# AllSerial.net
KiCad netlist of a schematic drawn in EAGLE
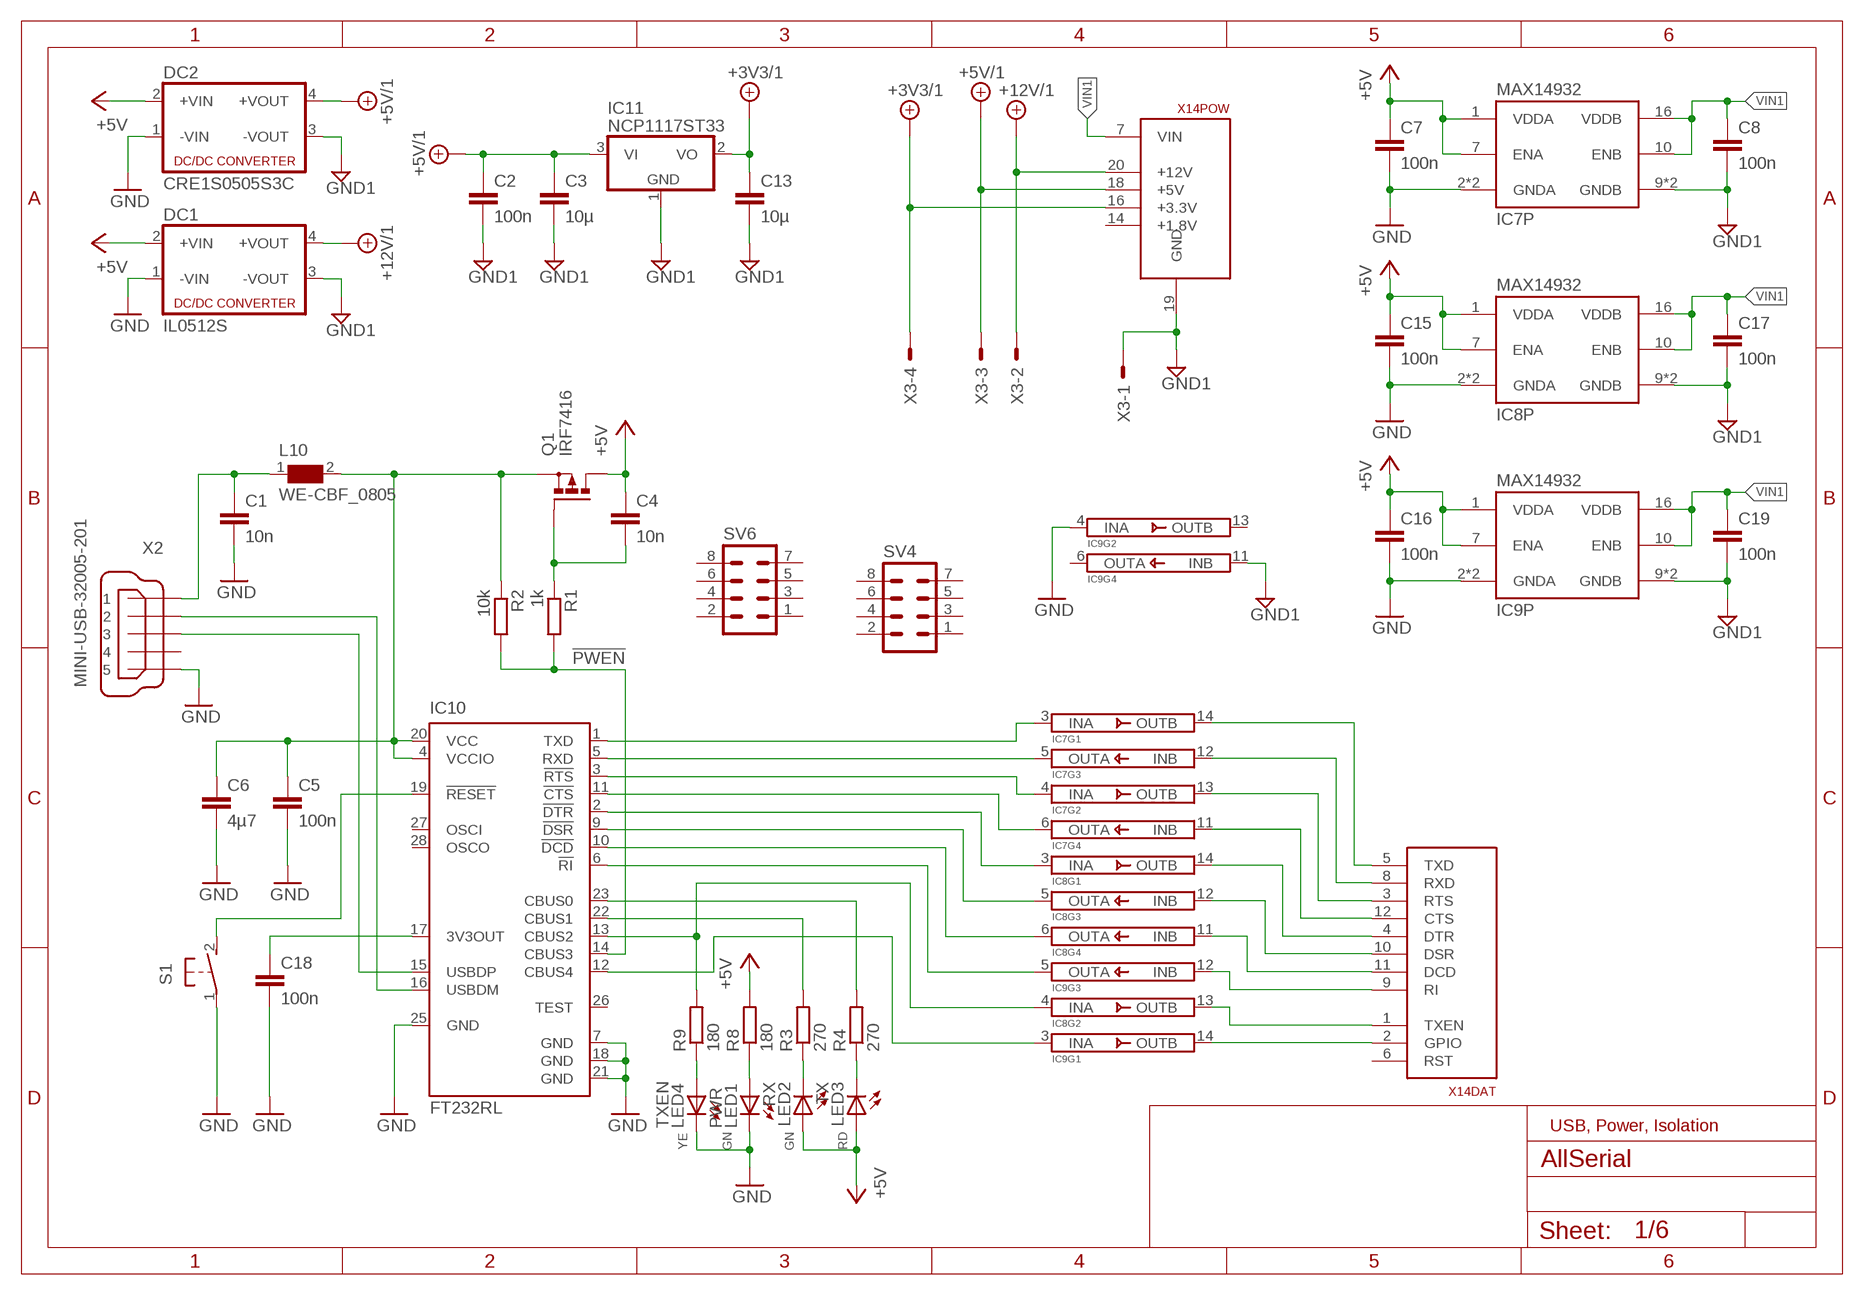
[diagram p0: schematic, sheet 1]
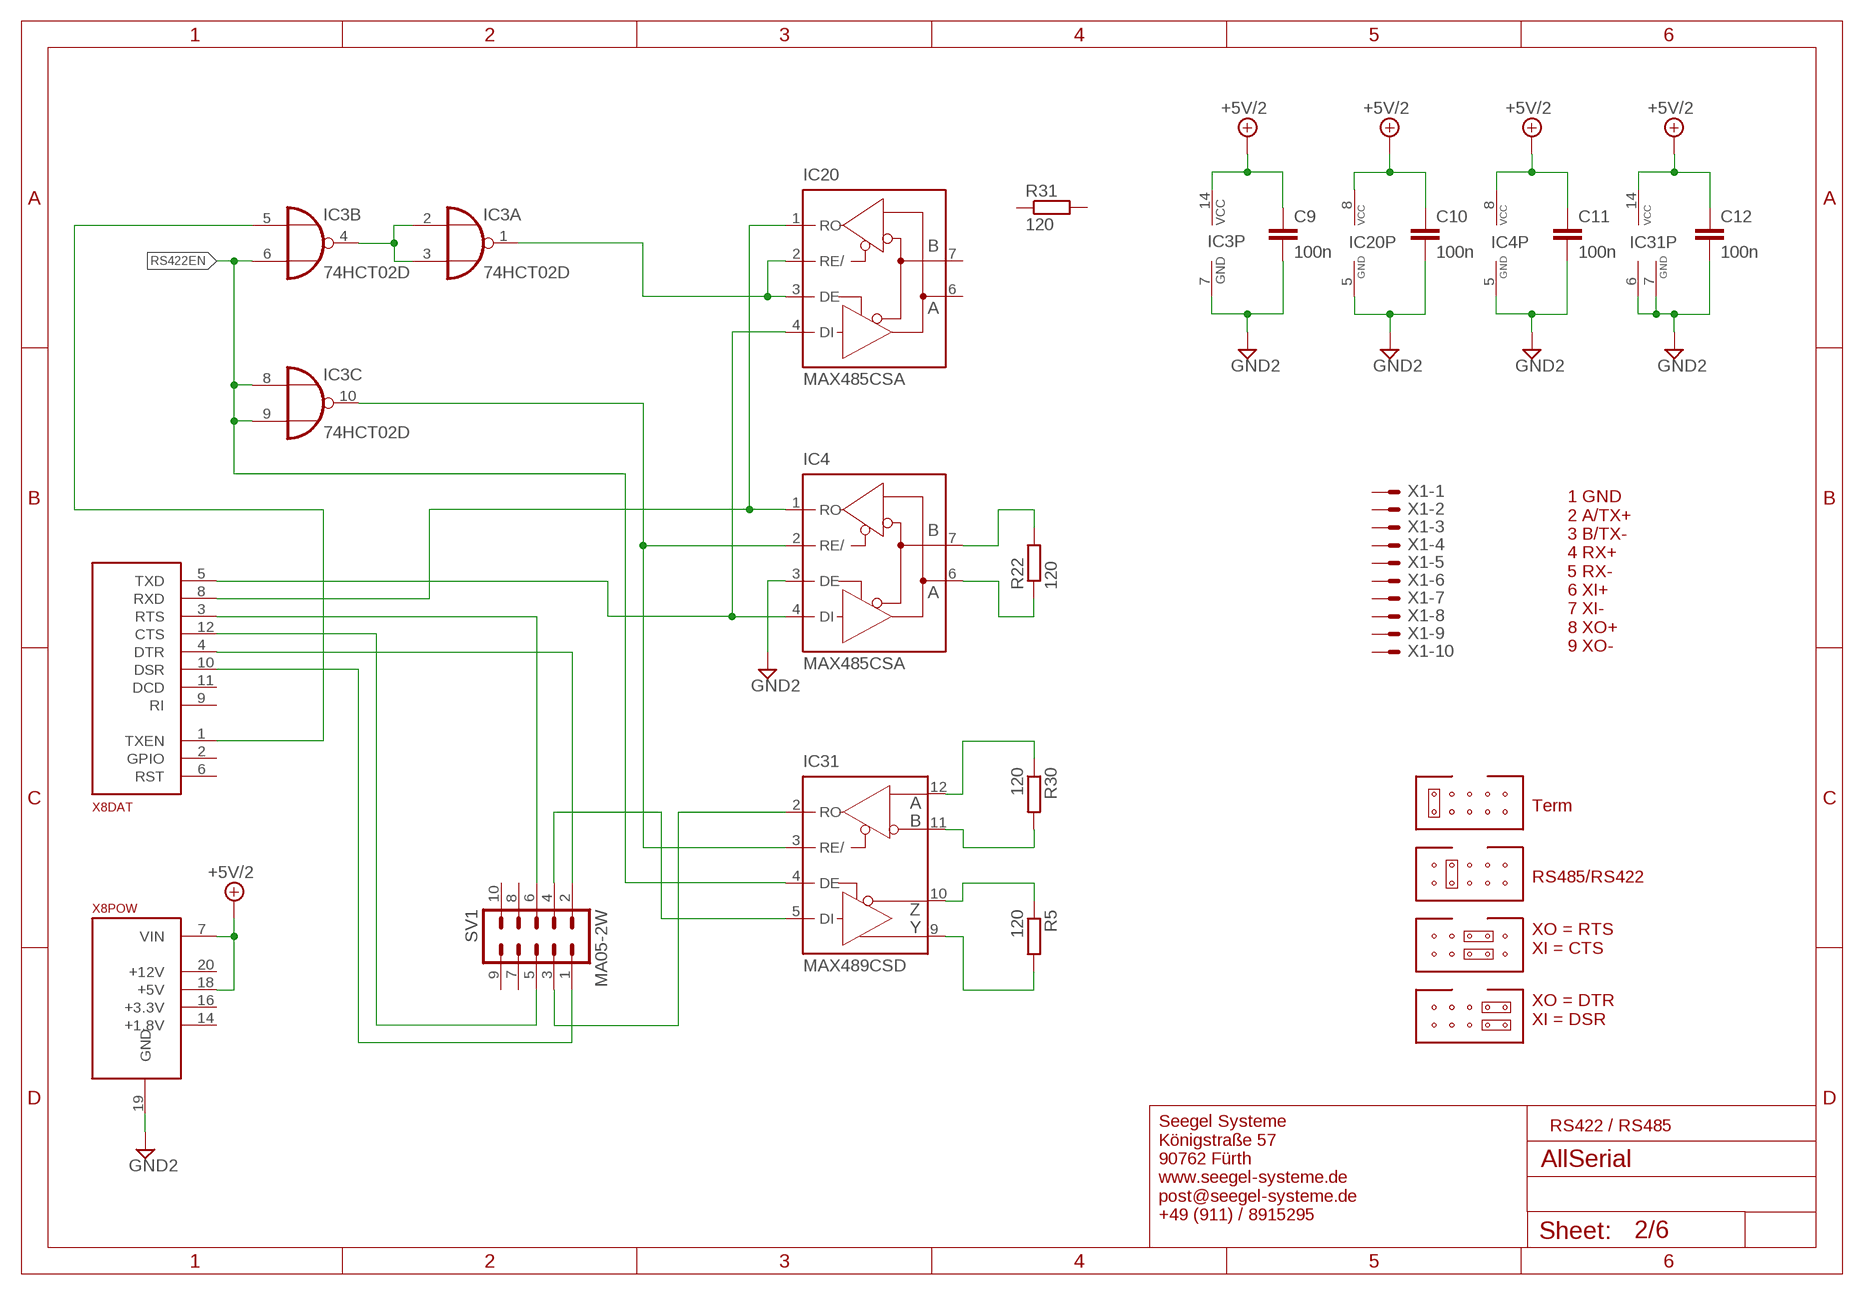
[diagram p1: schematic, sheet 2]
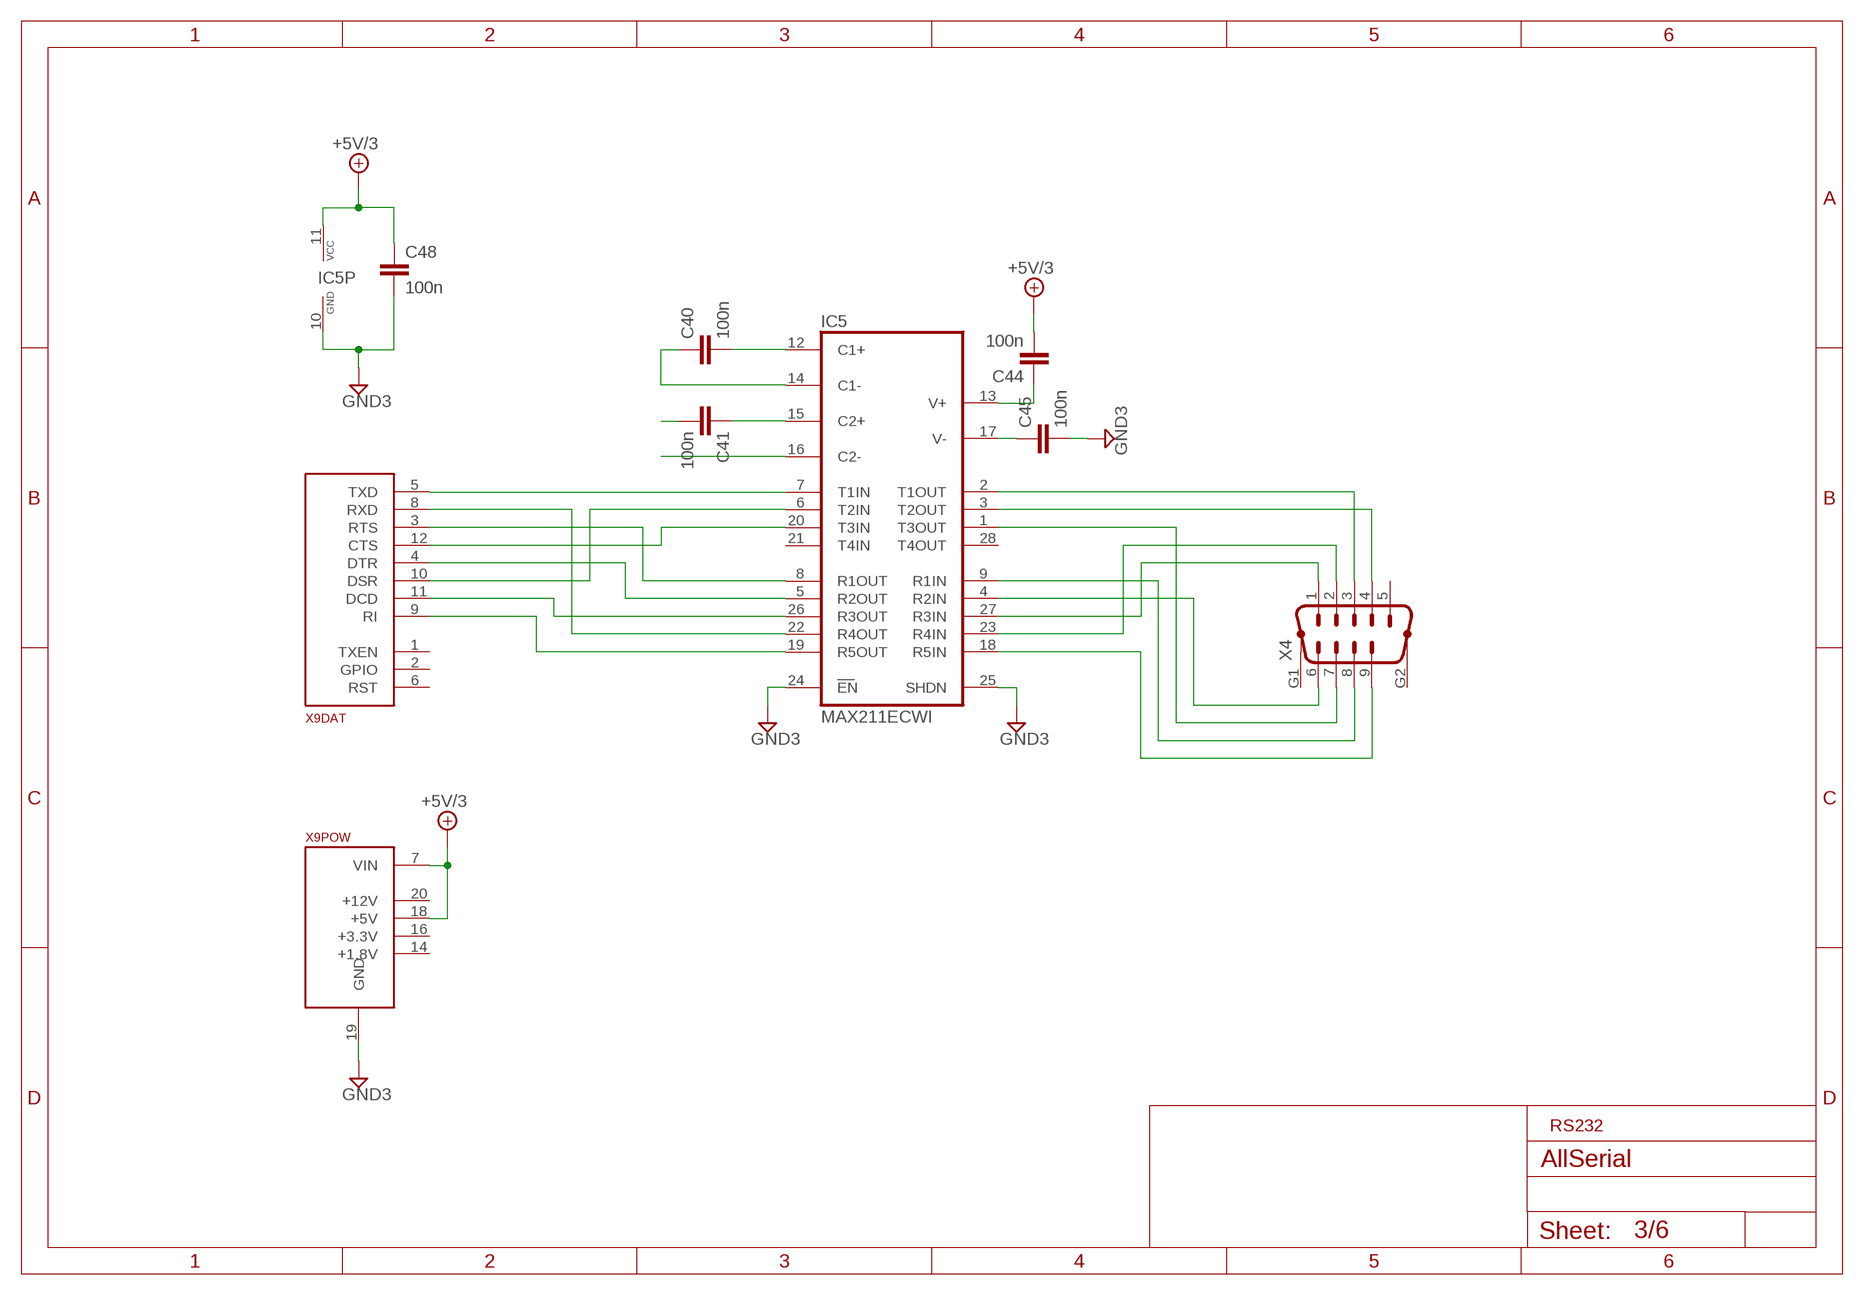
[diagram p2: schematic, sheet 3]
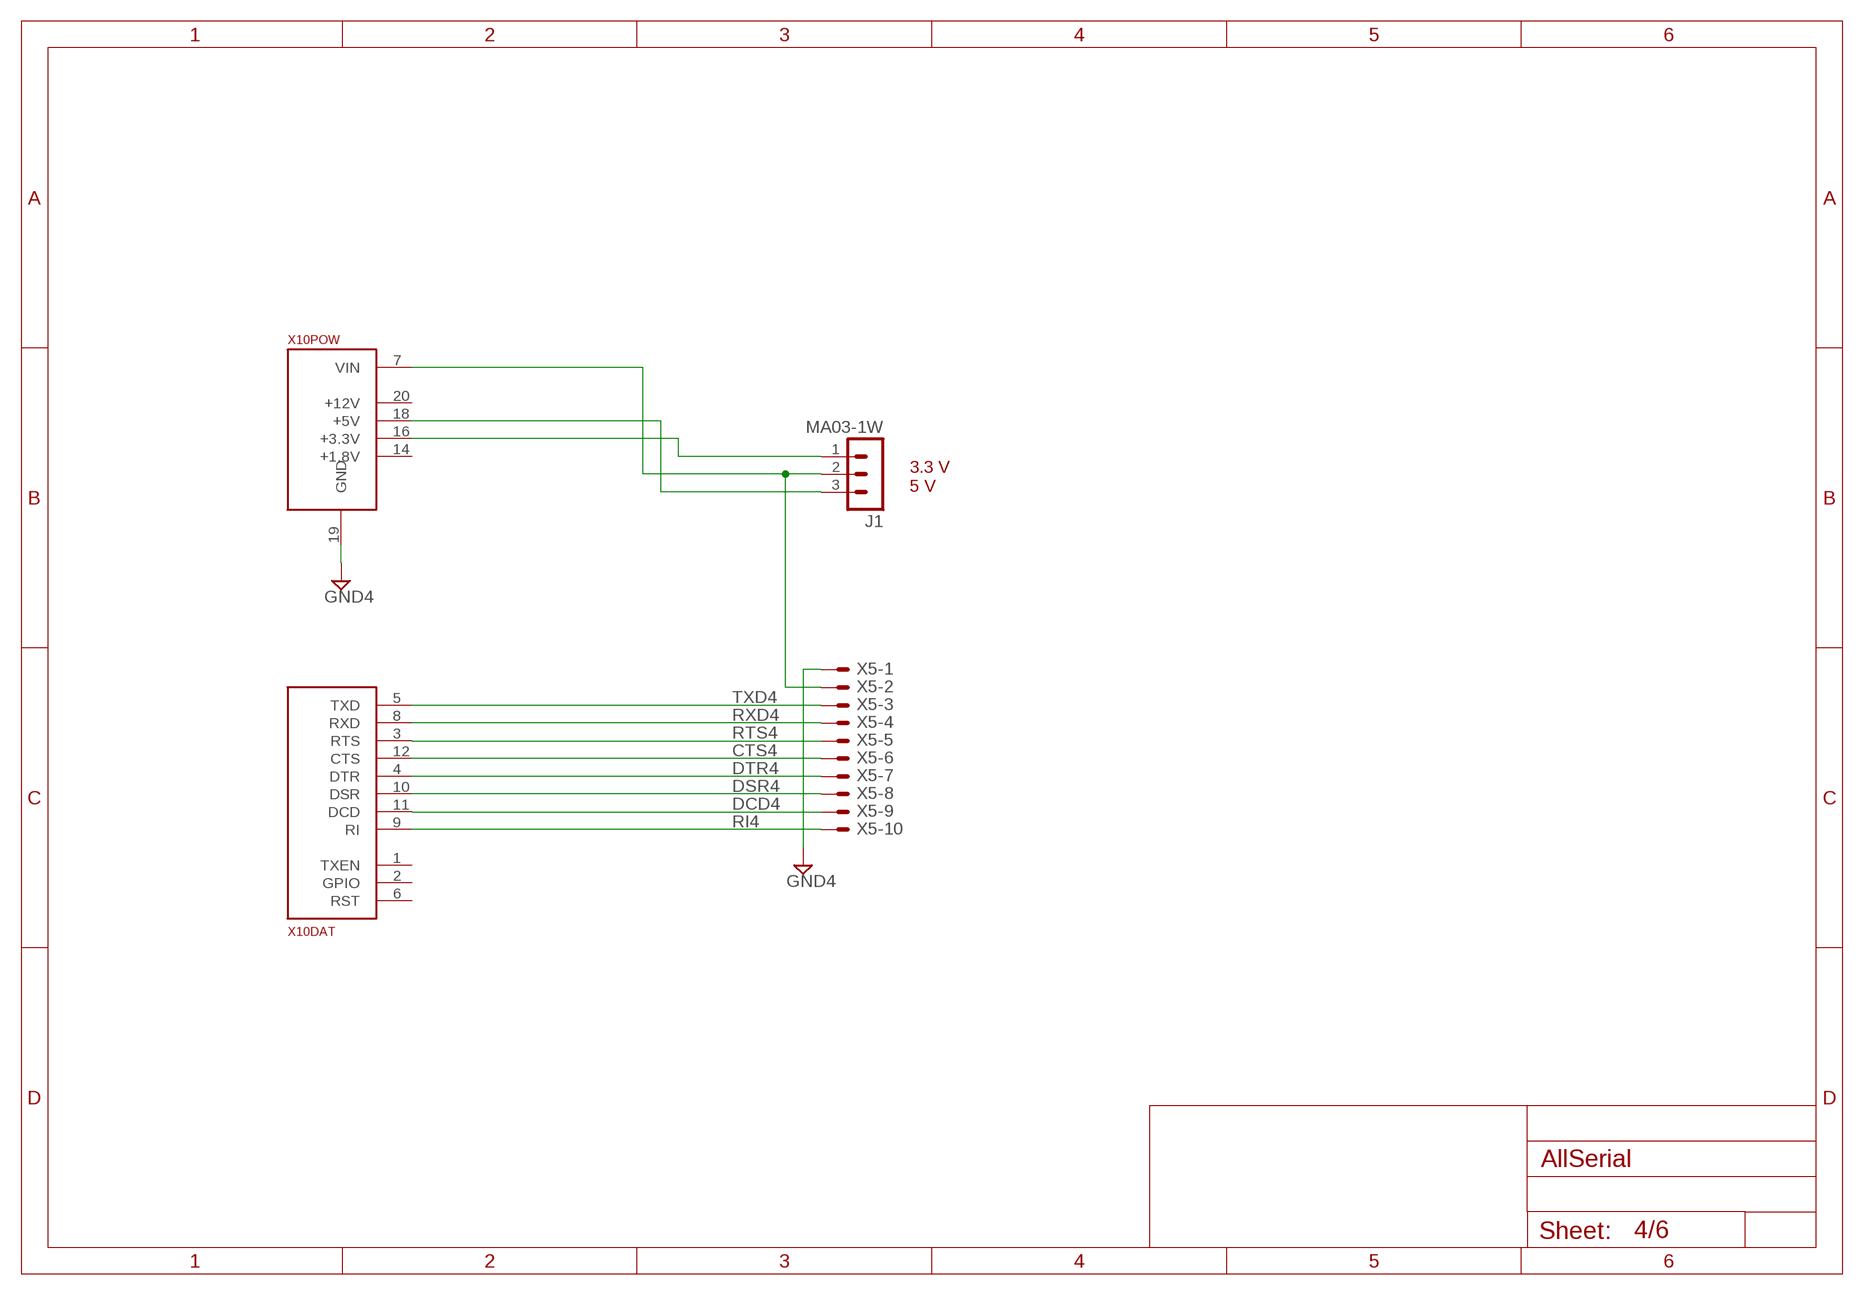
[diagram p3: schematic, sheet 4]
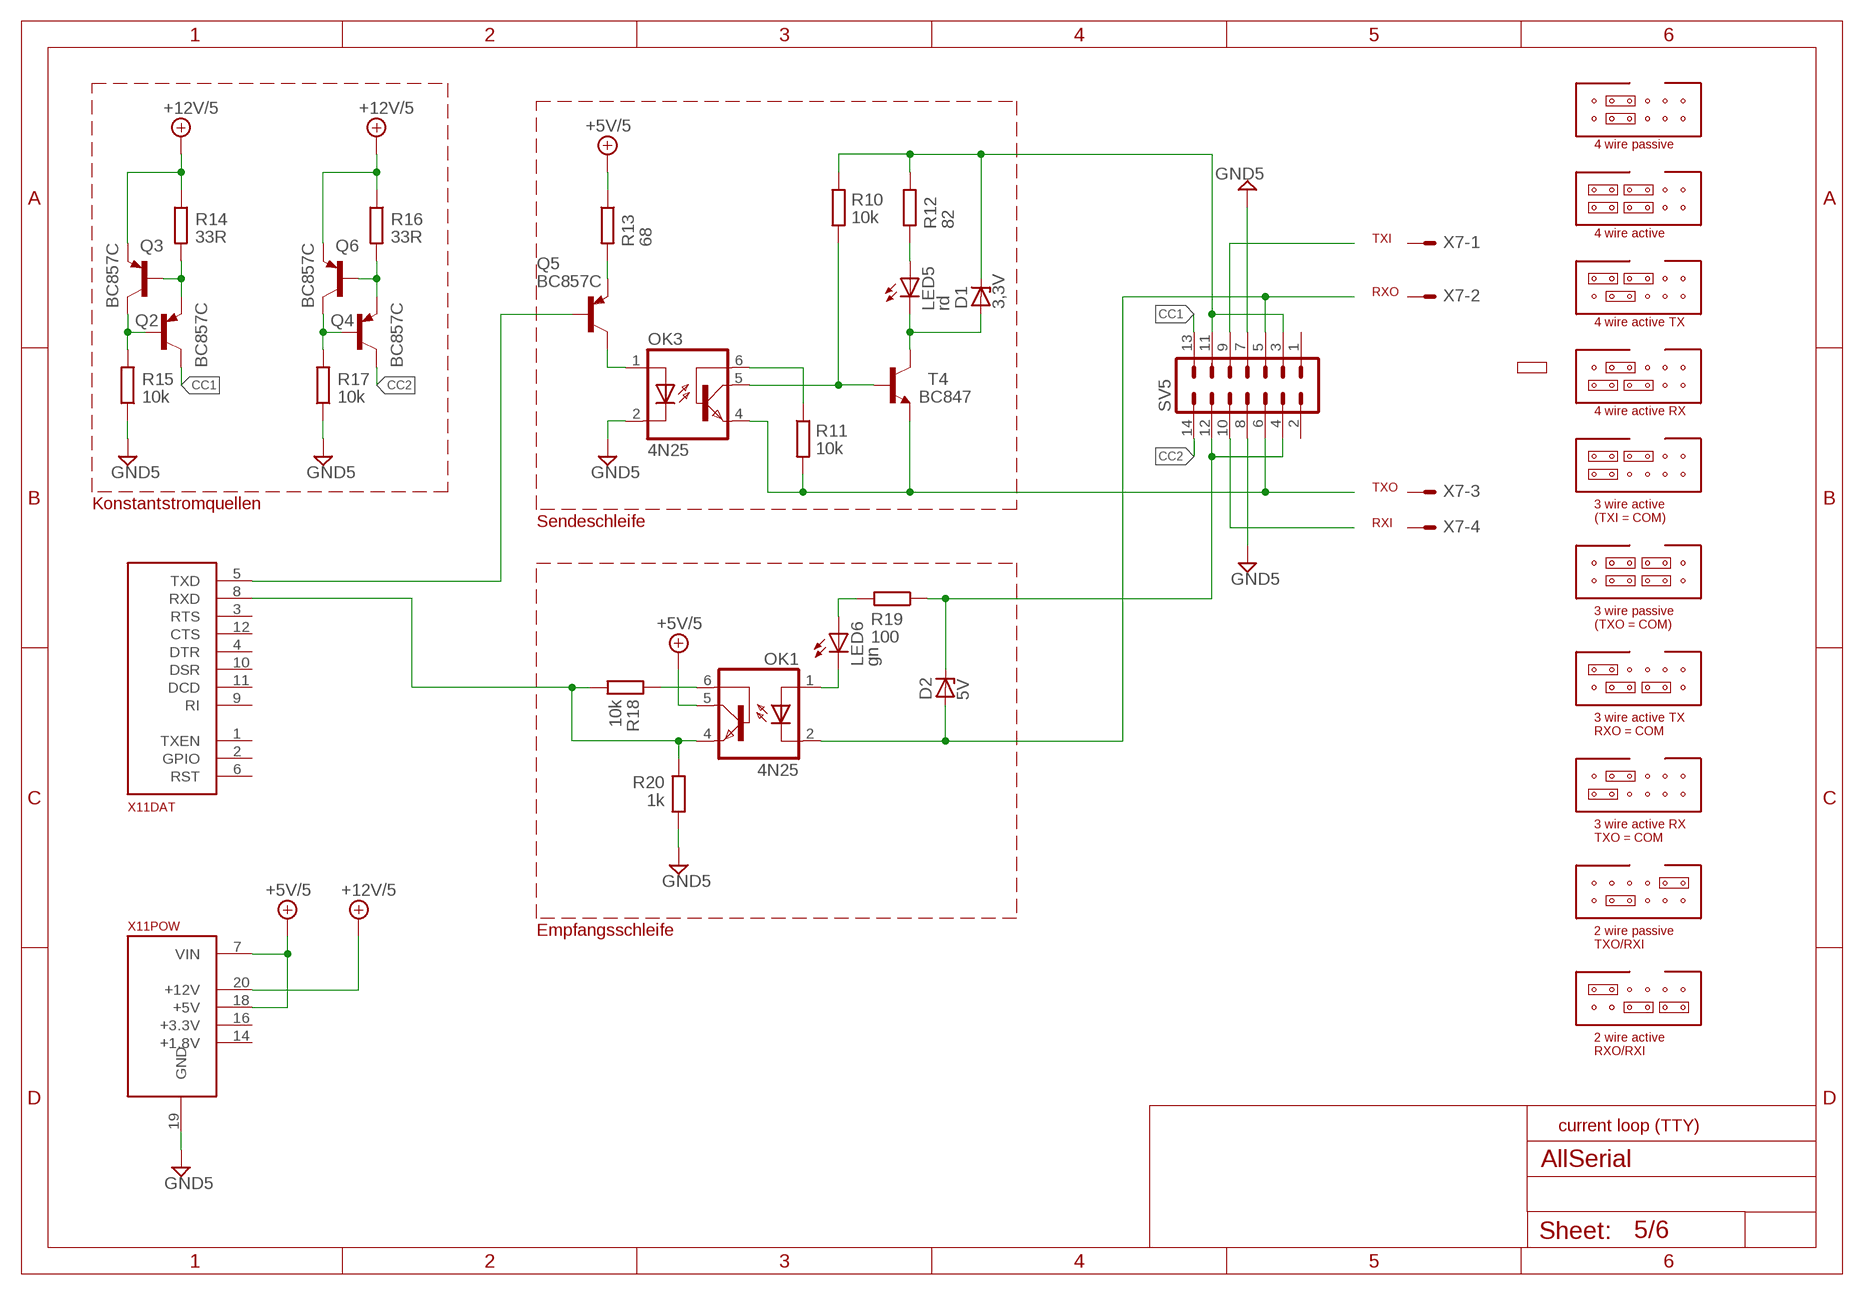
[diagram p4: schematic, sheet 5]
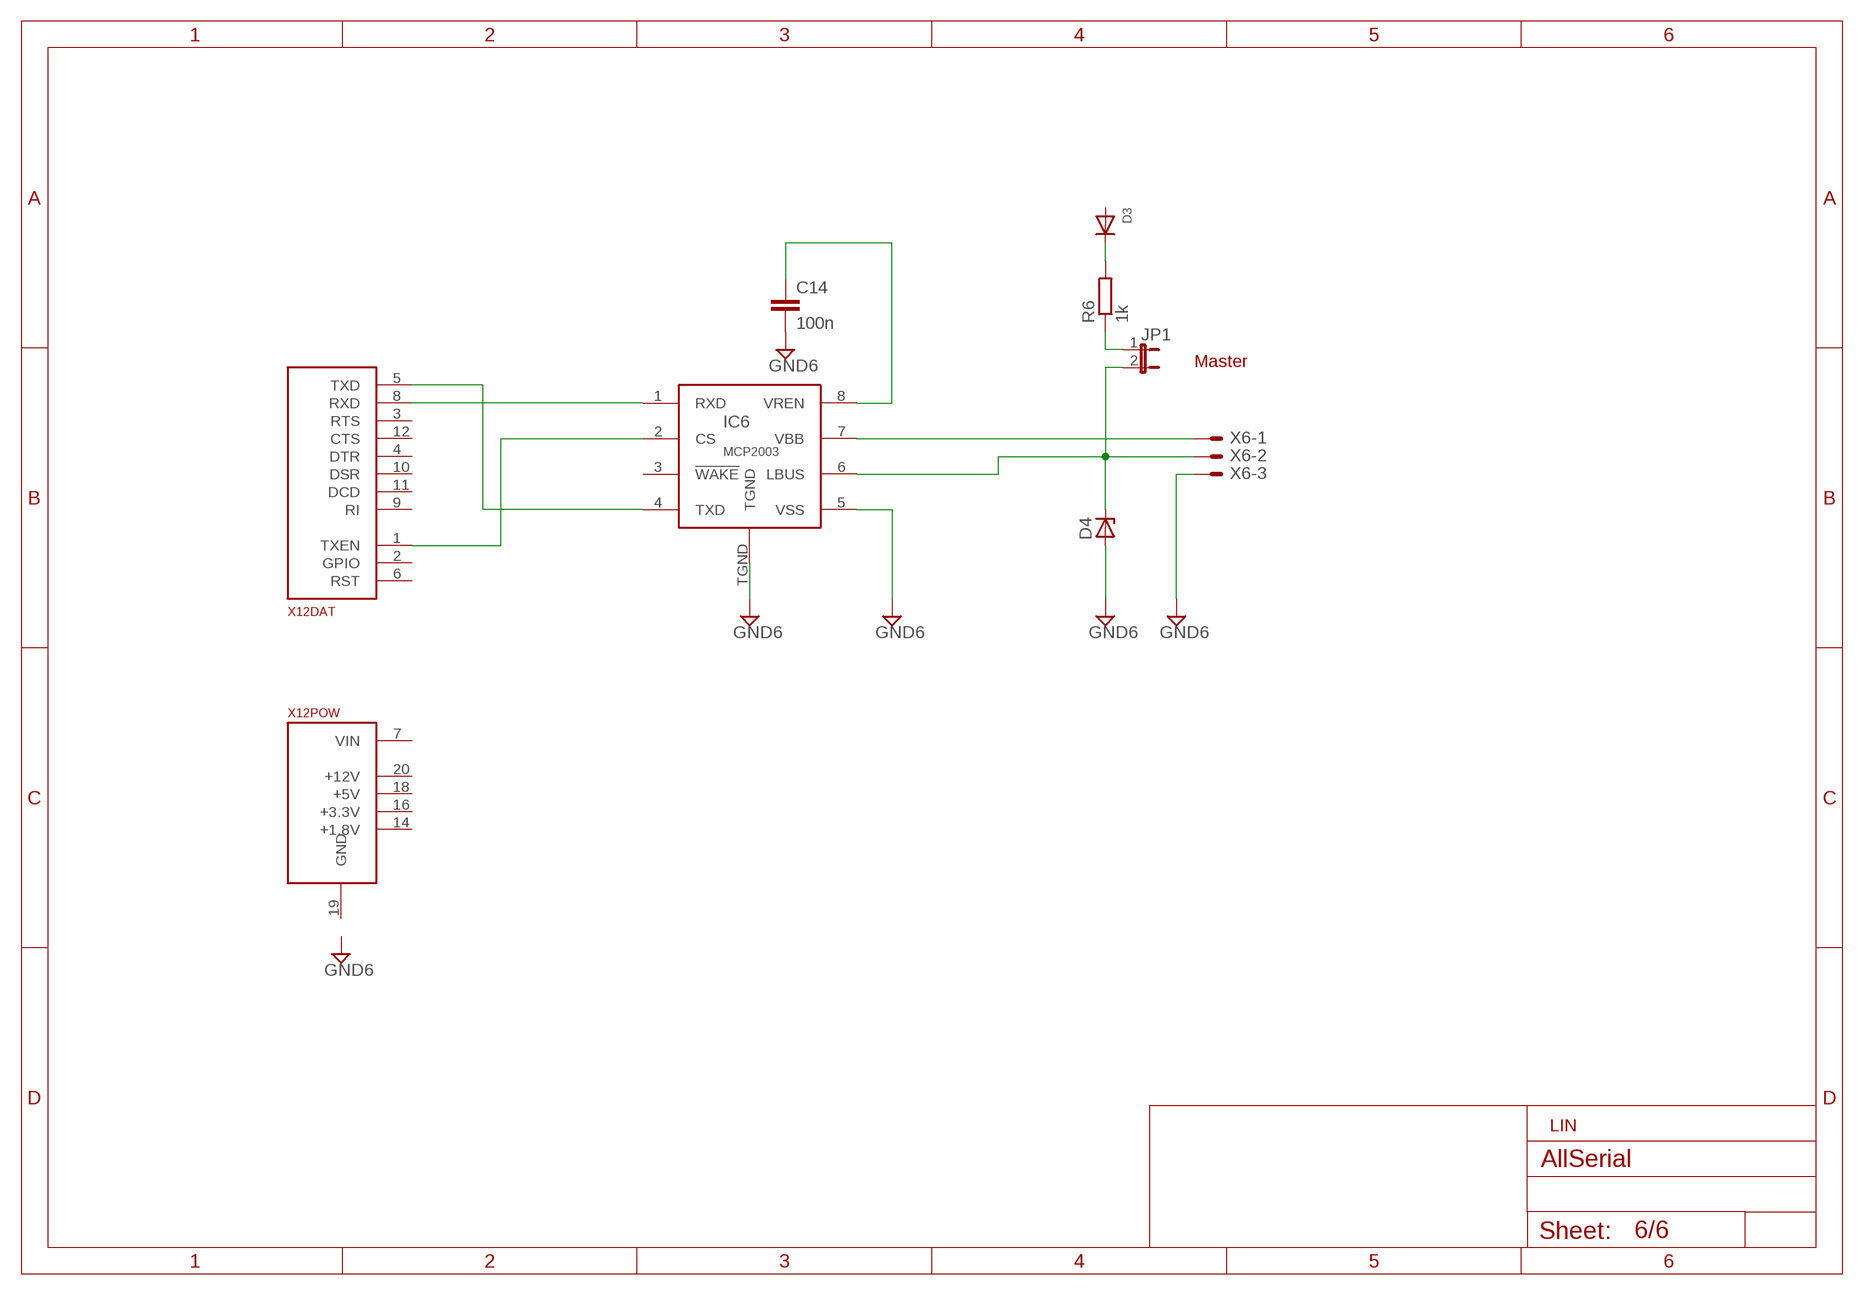
[diagram p5: schematic, sheet 6]

(export (version "E")
  (design (tool "Eeschema 10.0.6"))
  (components
    (comp (ref "C1")
      (value "10n")
      (footprint "eagle-import:C0805")
      (libsource (lib "eagle-import") (part "C-EUC0805"))
    )
    (comp (ref "C2")
      (value "100n")
      (footprint "eagle-import:C0805")
      (libsource (lib "eagle-import") (part "C-EUC0805"))
    )
    (comp (ref "C3")
      (value "10µ")
      (footprint "eagle-import:C0805")
      (libsource (lib "eagle-import") (part "C-EUC0805"))
    )
    (comp (ref "C4")
      (value "10n")
      (footprint "eagle-import:C0805")
      (libsource (lib "eagle-import") (part "C-EUC0805"))
    )
    (comp (ref "C5")
      (value "100n")
      (footprint "eagle-import:C0805")
      (libsource (lib "eagle-import") (part "C-EUC0805"))
    )
    (comp (ref "C6")
      (value "4µ7")
      (footprint "eagle-import:C0805")
      (libsource (lib "eagle-import") (part "C-EUC0805"))
    )
    (comp (ref "C7")
      (value "100n")
      (footprint "eagle-import:C0805")
      (libsource (lib "eagle-import") (part "C-EUC0805"))
    )
    (comp (ref "C8")
      (value "100n")
      (footprint "eagle-import:C0805")
      (libsource (lib "eagle-import") (part "C-EUC0805"))
    )
    (comp (ref "C13")
      (value "10µ")
      (footprint "eagle-import:C0805")
      (libsource (lib "eagle-import") (part "C-EUC0805"))
    )
    (comp (ref "C15")
      (value "100n")
      (footprint "eagle-import:C0805")
      (libsource (lib "eagle-import") (part "C-EUC0805"))
    )
    (comp (ref "C16")
      (value "100n")
      (footprint "eagle-import:C0805")
      (libsource (lib "eagle-import") (part "C-EUC0805"))
    )
    (comp (ref "C17")
      (value "100n")
      (footprint "eagle-import:C0805")
      (libsource (lib "eagle-import") (part "C-EUC0805"))
    )
    (comp (ref "C18")
      (value "100n")
      (footprint "eagle-import:C0805")
      (libsource (lib "eagle-import") (part "C-EUC0805"))
    )
    (comp (ref "C19")
      (value "100n")
      (footprint "eagle-import:C0805")
      (libsource (lib "eagle-import") (part "C-EUC0805"))
    )
    (comp (ref "DC1")
      (value "IL0512S")
      (footprint "eagle-import:NME")
      (fields (field (name "MF") "C & D TECHNOLOGIES, INC") (field (name "MPN") "NME1205D"))
      (libsource (lib "eagle-import") (part "NME"))
    )
    (comp (ref "DC2")
      (value "CRE1S0505S3C")
      (footprint "eagle-import:NME")
      (fields (field (name "MF") "C & D TECHNOLOGIES, INC") (field (name "MPN") "NME1205D"))
      (libsource (lib "eagle-import") (part "NME"))
    )
    (comp (ref "IC7")
      (value "MAX14932")
      (footprint "eagle-import:SO16")
      (libsource (lib "eagle-import") (part "MAX14932"))
    )
    (comp (ref "IC8")
      (value "MAX14932")
      (footprint "eagle-import:SO16")
      (libsource (lib "eagle-import") (part "MAX14932"))
    )
    (comp (ref "IC9")
      (value "MAX14932")
      (footprint "eagle-import:SO16")
      (libsource (lib "eagle-import") (part "MAX14932"))
    )
    (comp (ref "IC10")
      (value "FT232RL")
      (footprint "eagle-import:SSOP28")
      (libsource (lib "eagle-import") (part "FT232RL"))
    )
    (comp (ref "IC11")
      (value "NCP1117ST33")
      (footprint "eagle-import:SOT23")
      (libsource (lib "eagle-import") (part "MCP1703CB"))
    )
    (comp (ref "L10")
      (value "WE-CBF_0805")
      (footprint "eagle-import:0805")
      (libsource (lib "eagle-import") (part "WE-CBF_0805"))
    )
    (comp (ref "LED1")
      (value "PWR")
      (footprint "eagle-import:CHIPLED_0805")
      (fields (field (name "COLOR") "GN"))
      (libsource (lib "eagle-import") (part "LEDCHIPLED_0805"))
    )
    (comp (ref "LED2")
      (value "RX")
      (footprint "eagle-import:CHIPLED_0805")
      (fields (field (name "COLOR") "GN"))
      (libsource (lib "eagle-import") (part "LEDCHIPLED_0805"))
    )
    (comp (ref "LED3")
      (value "TX")
      (footprint "eagle-import:CHIPLED_0805")
      (fields (field (name "COLOR") "RD"))
      (libsource (lib "eagle-import") (part "LEDCHIPLED_0805"))
    )
    (comp (ref "LED4")
      (value "TXEN")
      (footprint "eagle-import:CHIPLED_0805")
      (fields (field (name "COLOR") "YE"))
      (libsource (lib "eagle-import") (part "LEDCHIPLED_0805"))
    )
    (comp (ref "Q1")
      (value "IRF7416")
      (footprint "eagle-import:SO-08")
      (libsource (lib "eagle-import") (part "P-MOSFET-SO8"))
    )
    (comp (ref "R1")
      (value "1k")
      (footprint "eagle-import:R0805")
      (libsource (lib "eagle-import") (part "R-EU_R0805"))
    )
    (comp (ref "R2")
      (value "10k")
      (footprint "eagle-import:R0805")
      (libsource (lib "eagle-import") (part "R-EU_R0805"))
    )
    (comp (ref "R3")
      (value "270")
      (footprint "eagle-import:R0805")
      (libsource (lib "eagle-import") (part "R-EU_R0805"))
    )
    (comp (ref "R4")
      (value "270")
      (footprint "eagle-import:R0805")
      (libsource (lib "eagle-import") (part "R-EU_R0805"))
    )
    (comp (ref "R8")
      (value "180")
      (footprint "eagle-import:R0805")
      (libsource (lib "eagle-import") (part "R-EU_R0805"))
    )
    (comp (ref "R9")
      (value "180")
      (footprint "eagle-import:R0805")
      (libsource (lib "eagle-import") (part "R-EU_R0805"))
    )
    (comp (ref "S1")
      (value "31-XX")
      (footprint "eagle-import:B3F-31XX")
      (fields (field (name "MPN") "B3F-3100"))
      (libsource (lib "eagle-import") (part "31-XX"))
    )
    (comp (ref "SV4")
      (value "MA04-2")
      (footprint "eagle-import:MA04-2")
      (libsource (lib "eagle-import") (part "MA04-2"))
    )
    (comp (ref "SV6")
      (value "MA04-2")
      (footprint "eagle-import:MA04-2")
      (libsource (lib "eagle-import") (part "MA04-2"))
    )
    (comp (ref "X2")
      (value "MINI-USB-32005-201")
      (footprint "eagle-import:32005-201")
      (libsource (lib "eagle-import") (part "MINI-USB-32005-201"))
    )
    (comp (ref "X3")
      (value "AKL18X-04W")
      (footprint "eagle-import:AKL182-04")
      (libsource (lib "eagle-import") (part "AKL18X-04W"))
    )
    (comp (ref "X14")
      (value "ALLSERIALMM")
      (footprint "eagle-import:MAIN-THT")
      (libsource (lib "eagle-import") (part "ALLSERIALMM"))
    )
    (comp (ref "C40")
      (value "100n")
      (footprint "eagle-import:C0805")
      (libsource (lib "eagle-import") (part "C-EUC0805"))
    )
    (comp (ref "C41")
      (value "100n")
      (footprint "eagle-import:C0805")
      (libsource (lib "eagle-import") (part "C-EUC0805"))
    )
    (comp (ref "C44")
      (value "100n")
      (footprint "eagle-import:C0805")
      (libsource (lib "eagle-import") (part "C-EUC0805"))
    )
    (comp (ref "C45")
      (value "100n")
      (footprint "eagle-import:C0805")
      (libsource (lib "eagle-import") (part "C-EUC0805"))
    )
    (comp (ref "C48")
      (value "100n")
      (footprint "eagle-import:C0805")
      (libsource (lib "eagle-import") (part "C-EUC0805"))
    )
    (comp (ref "IC5")
      (value "MAX211ECWI")
      (footprint "eagle-import:SO28L")
      (fields (field (name "MPN") "MAX211ECWI+T"))
      (libsource (lib "eagle-import") (part "MAX211ECWI"))
    )
    (comp (ref "X4")
      (value "M09HP")
      (footprint "eagle-import:M09HP")
      (libsource (lib "eagle-import") (part "M09HP"))
    )
    (comp (ref "X9")
      (value "ALLSERIALD")
      (footprint "eagle-import:DAUGHTER-THT")
      (libsource (lib "eagle-import") (part "ALLSERIALD"))
    )
    (comp (ref "C9")
      (value "100n")
      (footprint "eagle-import:C0805")
      (libsource (lib "eagle-import") (part "C-EUC0805"))
    )
    (comp (ref "C10")
      (value "100n")
      (footprint "eagle-import:C0805")
      (libsource (lib "eagle-import") (part "C-EUC0805"))
    )
    (comp (ref "C11")
      (value "100n")
      (footprint "eagle-import:C0805")
      (libsource (lib "eagle-import") (part "C-EUC0805"))
    )
    (comp (ref "C12")
      (value "100n")
      (footprint "eagle-import:C0805")
      (libsource (lib "eagle-import") (part "C-EUC0805"))
    )
    (comp (ref "IC3")
      (value "74HCT02D")
      (footprint "eagle-import:SO14")
      (libsource (lib "eagle-import") (part "7402DHCT"))
    )
    (comp (ref "IC4")
      (value "MAX485CSA")
      (footprint "eagle-import:SO08")
      (fields (field (name "MF") "MAXIM") (field (name "MPN") "MAX481CSA"))
      (libsource (lib "eagle-import") (part "MAX481CSA"))
    )
    (comp (ref "IC20")
      (value "MAX485CSA")
      (footprint "eagle-import:SO08")
      (fields (field (name "MF") "MAXIM") (field (name "MPN") "MAX481CSA"))
      (libsource (lib "eagle-import") (part "MAX481CSA"))
    )
    (comp (ref "IC31")
      (value "MAX489CSD")
      (footprint "eagle-import:SO14")
      (fields (field (name "MF") "MAXIM"))
      (libsource (lib "eagle-import") (part "MAX489CSD"))
    )
    (comp (ref "R5")
      (value "120")
      (footprint "eagle-import:R0805")
      (libsource (lib "eagle-import") (part "R-EU_R0805"))
    )
    (comp (ref "R22")
      (value "120")
      (footprint "eagle-import:R0805")
      (libsource (lib "eagle-import") (part "R-EU_R0805"))
    )
    (comp (ref "R30")
      (value "120")
      (footprint "eagle-import:R0805")
      (libsource (lib "eagle-import") (part "R-EU_R0805"))
    )
    (comp (ref "R31")
      (value "120")
      (footprint "eagle-import:R0805")
      (libsource (lib "eagle-import") (part "R-EU_R0805"))
    )
    (comp (ref "SV1")
      (value "MA05-2W")
      (footprint "eagle-import:MA05-2W")
      (libsource (lib "eagle-import") (part "MA05-2W"))
    )
    (comp (ref "X1")
      (value "AKL18X-10W")
      (footprint "eagle-import:AKL182-10")
      (libsource (lib "eagle-import") (part "AKL18X-10W"))
    )
    (comp (ref "X8")
      (value "ALLSERIALD")
      (footprint "eagle-import:DAUGHTER-THT")
      (libsource (lib "eagle-import") (part "ALLSERIALD"))
    )
    (comp (ref "C14")
      (value "100n")
      (footprint "eagle-import:C0805")
      (libsource (lib "eagle-import") (part "C-EUC0805"))
    )
    (comp (ref "D3")
      (value "DIODESOD-123")
      (footprint "eagle-import:SOD-123")
      (libsource (lib "eagle-import") (part "DIODESOD-123"))
    )
    (comp (ref "D4")
      (value "ZENER-DIODESOT23")
      (footprint "eagle-import:SOT23")
      (libsource (lib "eagle-import") (part "ZENER-DIODESOT23"))
    )
    (comp (ref "IC6")
      (value "MCP2003")
      (footprint "eagle-import:SOIC8T")
      (libsource (lib "eagle-import") (part "MCP2003"))
    )
    (comp (ref "JP1")
      (value "JP1E")
      (footprint "eagle-import:JP1")
      (libsource (lib "eagle-import") (part "JP1E"))
    )
    (comp (ref "R6")
      (value "1k")
      (footprint "eagle-import:R0805")
      (libsource (lib "eagle-import") (part "R-EU_R0805"))
    )
    (comp (ref "X6")
      (value "AKL18X-03W")
      (footprint "eagle-import:AKL182-03")
      (libsource (lib "eagle-import") (part "AKL18X-03W"))
    )
    (comp (ref "X12")
      (value "ALLSERIALD")
      (footprint "eagle-import:DAUGHTER-THT")
      (libsource (lib "eagle-import") (part "ALLSERIALD"))
    )
    (comp (ref "J1")
      (value "MA03-1W")
      (footprint "eagle-import:MA03-1W")
      (libsource (lib "eagle-import") (part "MA03-1W"))
    )
    (comp (ref "X5")
      (value "AKL18X-10W")
      (footprint "eagle-import:AKL182-10")
      (libsource (lib "eagle-import") (part "AKL18X-10W"))
    )
    (comp (ref "X10")
      (value "ALLSERIALD")
      (footprint "eagle-import:DAUGHTER-THT")
      (libsource (lib "eagle-import") (part "ALLSERIALD"))
    )
    (comp (ref "D1")
      (value "3,3V")
      (footprint "eagle-import:SOT23")
      (libsource (lib "eagle-import") (part "ZENER-DIODESOT23"))
    )
    (comp (ref "D2")
      (value "5V")
      (footprint "eagle-import:SOT23")
      (libsource (lib "eagle-import") (part "ZENER-DIODESOT23"))
    )
    (comp (ref "LED5")
      (value "rd")
      (footprint "eagle-import:CHIPLED_0603")
      (libsource (lib "eagle-import") (part "LEDCHIPLED_0603"))
    )
    (comp (ref "LED6")
      (value "gn")
      (footprint "eagle-import:CHIPLED_0603")
      (libsource (lib "eagle-import") (part "LEDCHIPLED_0603"))
    )
    (comp (ref "OK1")
      (value "4N25")
      (footprint "eagle-import:DIL06")
      (fields (field (name "MF") "FAIRCHILD SEMICONDUCTOR") (field (name "MPN") "4N35"))
      (libsource (lib "eagle-import") (part "4N35"))
    )
    (comp (ref "OK3")
      (value "4N25")
      (footprint "eagle-import:DIL06")
      (fields (field (name "MF") "FAIRCHILD SEMICONDUCTOR") (field (name "MPN") "4N35"))
      (libsource (lib "eagle-import") (part "4N35"))
    )
    (comp (ref "Q2")
      (value "BC857C")
      (footprint "eagle-import:SOT23-BEC")
      (libsource (lib "eagle-import") (part "BC857SMDC"))
    )
    (comp (ref "Q3")
      (value "BC857C")
      (footprint "eagle-import:SOT23-BEC")
      (libsource (lib "eagle-import") (part "BC857SMDC"))
    )
    (comp (ref "Q4")
      (value "BC857C")
      (footprint "eagle-import:SOT23-BEC")
      (libsource (lib "eagle-import") (part "BC857SMDC"))
    )
    (comp (ref "Q5")
      (value "BC857C")
      (footprint "eagle-import:SOT23-BEC")
      (libsource (lib "eagle-import") (part "BC857SMDC"))
    )
    (comp (ref "Q6")
      (value "BC857C")
      (footprint "eagle-import:SOT23-BEC")
      (libsource (lib "eagle-import") (part "BC857SMDC"))
    )
    (comp (ref "R10")
      (value "10k")
      (footprint "eagle-import:R0805")
      (libsource (lib "eagle-import") (part "resistor_R-EU_R0805"))
    )
    (comp (ref "R11")
      (value "10k")
      (footprint "eagle-import:R0805")
      (libsource (lib "eagle-import") (part "resistor_R-EU_R0805"))
    )
    (comp (ref "R12")
      (value "82")
      (footprint "eagle-import:R0805")
      (libsource (lib "eagle-import") (part "resistor_R-EU_R0805"))
    )
    (comp (ref "R13")
      (value "68")
      (footprint "eagle-import:R0805")
      (libsource (lib "eagle-import") (part "resistor_R-EU_R0805"))
    )
    (comp (ref "R14")
      (value "33R")
      (footprint "eagle-import:R0805")
      (libsource (lib "eagle-import") (part "resistor_R-EU_R0805"))
    )
    (comp (ref "R15")
      (value "10k")
      (footprint "eagle-import:R0805")
      (libsource (lib "eagle-import") (part "resistor_R-EU_R0805"))
    )
    (comp (ref "R16")
      (value "33R")
      (footprint "eagle-import:R0805")
      (libsource (lib "eagle-import") (part "resistor_R-EU_R0805"))
    )
    (comp (ref "R17")
      (value "10k")
      (footprint "eagle-import:R0805")
      (libsource (lib "eagle-import") (part "resistor_R-EU_R0805"))
    )
    (comp (ref "R18")
      (value "10k")
      (footprint "eagle-import:R0805")
      (libsource (lib "eagle-import") (part "resistor_R-EU_R0805"))
    )
    (comp (ref "R19")
      (value "100")
      (footprint "eagle-import:R0805")
      (libsource (lib "eagle-import") (part "resistor_R-EU_R0805"))
    )
    (comp (ref "R20")
      (value "1k")
      (footprint "eagle-import:R0805")
      (libsource (lib "eagle-import") (part "resistor_R-EU_R0805"))
    )
    (comp (ref "SV5")
      (value "ML14L")
      (footprint "eagle-import:ML14L")
      (libsource (lib "eagle-import") (part "ML14L"))
    )
    (comp (ref "T4")
      (value "BC847")
      (footprint "eagle-import:SOT23")
      (libsource (lib "eagle-import") (part "BC847"))
    )
    (comp (ref "X7")
      (value "AKL18X-04W")
      (footprint "eagle-import:AKL182-04")
      (libsource (lib "eagle-import") (part "AKL18X-04W"))
    )
    (comp (ref "X11")
      (value "ALLSERIALD")
      (footprint "eagle-import:DAUGHTER-THT")
      (libsource (lib "eagle-import") (part "ALLSERIALD"))
    )
  )
  (nets
    (net (code "1") (name "+3V3{slash}1") (class "Default")
      (node (ref "C13") (pin "1") (pinfunction "1_1") (pintype "passive"))
      (node (ref "IC11") (pin "2") (pinfunction "VO_2") (pintype "passive"))
      (node (ref "X14") (pin "16") (pinfunction "+3.3V_16") (pintype "bidirectional"))
      (node (ref "X3") (pin "P$4") (pinfunction "S_P$4") (pintype "passive"))
    )
    (net (code "2") (name "+5V") (class "Default")
      (node (ref "C15") (pin "1") (pinfunction "1_1") (pintype "passive"))
      (node (ref "C16") (pin "1") (pinfunction "1_1") (pintype "passive"))
      (node (ref "C4") (pin "1") (pinfunction "1_1") (pintype "passive"))
      (node (ref "C7") (pin "1") (pinfunction "1_1") (pintype "passive"))
      (node (ref "DC1") (pin "2") (pinfunction "+VIN_2") (pintype "passive"))
      (node (ref "DC2") (pin "2") (pinfunction "+VIN_2") (pintype "passive"))
      (node (ref "IC7") (pin "1") (pinfunction "VDDA_1") (pintype "power_in"))
      (node (ref "IC7") (pin "7") (pinfunction "ENA_7") (pintype "input"))
      (node (ref "IC8") (pin "1") (pinfunction "VDDA_1") (pintype "power_in"))
      (node (ref "IC8") (pin "7") (pinfunction "ENA_7") (pintype "input"))
      (node (ref "IC9") (pin "1") (pinfunction "VDDA_1") (pintype "power_in"))
      (node (ref "IC9") (pin "7") (pinfunction "ENA_7") (pintype "input"))
      (node (ref "LED2") (pin "A") (pinfunction "A_A") (pintype "passive"))
      (node (ref "LED3") (pin "A") (pinfunction "A_A") (pintype "passive"))
      (node (ref "Q1") (pin "5") (pinfunction "D_5") (pintype "passive"))
      (node (ref "Q1") (pin "6") (pinfunction "D_6") (pintype "passive"))
      (node (ref "Q1") (pin "7") (pinfunction "D_7") (pintype "passive"))
      (node (ref "Q1") (pin "8") (pinfunction "D_8") (pintype "passive"))
      (node (ref "R8") (pin "2") (pinfunction "2_2") (pintype "passive"))
    )
    (net (code "3") (name "+5V{slash}1") (class "Default")
      (node (ref "C2") (pin "1") (pinfunction "1_1") (pintype "passive"))
      (node (ref "C3") (pin "1") (pinfunction "1_1") (pintype "passive"))
      (node (ref "DC2") (pin "4") (pinfunction "+VOUT_4") (pintype "passive"))
      (node (ref "IC11") (pin "3") (pinfunction "VI_3") (pintype "input"))
      (node (ref "X14") (pin "18") (pinfunction "+5V_18") (pintype "bidirectional"))
      (node (ref "X3") (pin "P$3") (pinfunction "S_P$3") (pintype "passive"))
    )
    (net (code "4") (name "+5V{slash}2") (class "Default")
      (node (ref "C10") (pin "1") (pinfunction "1_1") (pintype "passive"))
      (node (ref "C11") (pin "1") (pinfunction "1_1") (pintype "passive"))
      (node (ref "C12") (pin "1") (pinfunction "1_1") (pintype "passive"))
      (node (ref "C9") (pin "1") (pinfunction "1_1") (pintype "passive"))
      (node (ref "IC20") (pin "8") (pinfunction "VCC_8") (pintype "power_in"))
      (node (ref "IC3") (pin "14") (pinfunction "VCC_14") (pintype "power_in"))
      (node (ref "IC31") (pin "14") (pinfunction "VCC_14") (pintype "power_in"))
      (node (ref "IC4") (pin "8") (pinfunction "VCC_8") (pintype "power_in"))
      (node (ref "X8") (pin "18") (pinfunction "+5V_18") (pintype "bidirectional"))
      (node (ref "X8") (pin "7") (pinfunction "VIN_7") (pintype "bidirectional"))
    )
    (net (code "5") (name "+5V{slash}3") (class "Default")
      (node (ref "C44") (pin "2") (pinfunction "2_2") (pintype "passive"))
      (node (ref "C48") (pin "1") (pinfunction "1_1") (pintype "passive"))
      (node (ref "IC5") (pin "11") (pinfunction "VCC_11") (pintype "power_in"))
      (node (ref "X9") (pin "18") (pinfunction "+5V_18") (pintype "bidirectional"))
      (node (ref "X9") (pin "7") (pinfunction "VIN_7") (pintype "bidirectional"))
    )
    (net (code "6") (name "+5V{slash}5") (class "Default")
      (node (ref "OK1") (pin "5") (pinfunction "COL_5") (pintype "passive"))
      (node (ref "R13") (pin "1") (pinfunction "1_1") (pintype "passive"))
      (node (ref "X11") (pin "18") (pinfunction "+5V_18") (pintype "bidirectional"))
      (node (ref "X11") (pin "7") (pinfunction "VIN_7") (pintype "bidirectional"))
    )
    (net (code "7") (name "+12V{slash}1") (class "Default")
      (node (ref "DC1") (pin "4") (pinfunction "+VOUT_4") (pintype "passive"))
      (node (ref "X14") (pin "20") (pinfunction "+12V_20") (pintype "bidirectional"))
      (node (ref "X3") (pin "P$2") (pinfunction "S_P$2") (pintype "passive"))
    )
    (net (code "8") (name "+12V{slash}5") (class "Default")
      (node (ref "Q3") (pin "E") (pinfunction "E_E") (pintype "passive"))
      (node (ref "Q6") (pin "E") (pinfunction "E_E") (pintype "passive"))
      (node (ref "R14") (pin "1") (pinfunction "1_1") (pintype "passive"))
      (node (ref "R16") (pin "1") (pinfunction "1_1") (pintype "passive"))
      (node (ref "X11") (pin "20") (pinfunction "+12V_20") (pintype "bidirectional"))
    )
    (net (code "9") (name "CC1") (class "Default")
      (node (ref "Q2") (pin "C") (pinfunction "C_C") (pintype "passive"))
      (node (ref "SV5") (pin "13") (pinfunction "13_13") (pintype "passive"))
    )
    (net (code "10") (name "CC2") (class "Default")
      (node (ref "Q4") (pin "C") (pinfunction "C_C") (pintype "passive"))
      (node (ref "SV5") (pin "14") (pinfunction "14_14") (pintype "passive"))
    )
    (net (code "11") (name "CTS4") (class "Default")
      (node (ref "X10") (pin "12") (pinfunction "CTS_12") (pintype "bidirectional"))
      (node (ref "X5") (pin "P$6") (pinfunction "S_P$6") (pintype "passive"))
    )
    (net (code "12") (name "DCD4") (class "Default")
      (node (ref "X10") (pin "11") (pinfunction "DCD_11") (pintype "bidirectional"))
      (node (ref "X5") (pin "P$9") (pinfunction "S_P$9") (pintype "passive"))
    )
    (net (code "13") (name "DSR4") (class "Default")
      (node (ref "X10") (pin "10") (pinfunction "DSR_10") (pintype "bidirectional"))
      (node (ref "X5") (pin "P$8") (pinfunction "S_P$8") (pintype "passive"))
    )
    (net (code "14") (name "DTR4") (class "Default")
      (node (ref "X10") (pin "4") (pinfunction "DTR_4") (pintype "bidirectional"))
      (node (ref "X5") (pin "P$7") (pinfunction "S_P$7") (pintype "passive"))
    )
    (net (code "15") (name "GND") (class "Default")
      (node (ref "C1") (pin "2") (pinfunction "2_2") (pintype "passive"))
      (node (ref "C15") (pin "2") (pinfunction "2_2") (pintype "passive"))
      (node (ref "C16") (pin "2") (pinfunction "2_2") (pintype "passive"))
      (node (ref "C18") (pin "2") (pinfunction "2_2") (pintype "passive"))
      (node (ref "C5") (pin "2") (pinfunction "2_2") (pintype "passive"))
      (node (ref "C6") (pin "2") (pinfunction "2_2") (pintype "passive"))
      (node (ref "C7") (pin "2") (pinfunction "2_2") (pintype "passive"))
      (node (ref "DC1") (pin "1") (pinfunction "-VIN_1") (pintype "passive"))
      (node (ref "DC2") (pin "1") (pinfunction "-VIN_1") (pintype "passive"))
      (node (ref "IC10") (pin "18") (pinfunction "GND_18") (pintype "power_in"))
      (node (ref "IC10") (pin "21") (pinfunction "GND_21") (pintype "power_in"))
      (node (ref "IC10") (pin "25") (pinfunction "GND_25") (pintype "power_in"))
      (node (ref "IC10") (pin "7") (pinfunction "GND_7") (pintype "power_in"))
      (node (ref "IC7") (pin "2") (pinfunction "GNDA_2") (pintype "power_in"))
      (node (ref "IC7") (pin "8") (pinfunction "GNDA_8") (pintype "power_in"))
      (node (ref "IC8") (pin "2") (pinfunction "GNDA_2") (pintype "power_in"))
      (node (ref "IC8") (pin "8") (pinfunction "GNDA_8") (pintype "power_in"))
      (node (ref "IC9") (pin "2") (pinfunction "GNDA_2") (pintype "power_in"))
      (node (ref "IC9") (pin "4") (pinfunction "INA_4") (pintype "input"))
      (node (ref "IC9") (pin "8") (pinfunction "GNDA_8") (pintype "power_in"))
      (node (ref "LED1") (pin "C") (pinfunction "C_C") (pintype "passive"))
      (node (ref "LED4") (pin "C") (pinfunction "C_C") (pintype "passive"))
      (node (ref "S1") (pin "1") (pinfunction "P_1") (pintype "passive"))
      (node (ref "X2") (pin "5") (pinfunction "5_5") (pintype "passive"))
    )
    (net (code "16") (name "GND1") (class "Default")
      (node (ref "C13") (pin "2") (pinfunction "2_2") (pintype "passive"))
      (node (ref "C17") (pin "2") (pinfunction "2_2") (pintype "passive"))
      (node (ref "C19") (pin "2") (pinfunction "2_2") (pintype "passive"))
      (node (ref "C2") (pin "2") (pinfunction "2_2") (pintype "passive"))
      (node (ref "C3") (pin "2") (pinfunction "2_2") (pintype "passive"))
      (node (ref "C8") (pin "2") (pinfunction "2_2") (pintype "passive"))
      (node (ref "DC1") (pin "3") (pinfunction "-VOUT_3") (pintype "passive"))
      (node (ref "DC2") (pin "3") (pinfunction "-VOUT_3") (pintype "passive"))
      (node (ref "IC11") (pin "1") (pinfunction "GND_1") (pintype "passive"))
      (node (ref "IC7") (pin "15") (pinfunction "GNDB_15") (pintype "power_in"))
      (node (ref "IC7") (pin "9") (pinfunction "GNDB_9") (pintype "power_in"))
      (node (ref "IC8") (pin "15") (pinfunction "GNDB_15") (pintype "power_in"))
      (node (ref "IC8") (pin "9") (pinfunction "GNDB_9") (pintype "power_in"))
      (node (ref "IC9") (pin "11") (pinfunction "INB_11") (pintype "input"))
      (node (ref "IC9") (pin "15") (pinfunction "GNDB_15") (pintype "power_in"))
      (node (ref "IC9") (pin "9") (pinfunction "GNDB_9") (pintype "power_in"))
      (node (ref "X14") (pin "19") (pinfunction "GND_19") (pintype "bidirectional"))
      (node (ref "X3") (pin "P$1") (pinfunction "S_P$1") (pintype "passive"))
    )
    (net (code "17") (name "GND2") (class "Default")
      (node (ref "C10") (pin "2") (pinfunction "2_2") (pintype "passive"))
      (node (ref "C11") (pin "2") (pinfunction "2_2") (pintype "passive"))
      (node (ref "C12") (pin "2") (pinfunction "2_2") (pintype "passive"))
      (node (ref "C9") (pin "2") (pinfunction "2_2") (pintype "passive"))
      (node (ref "IC20") (pin "5") (pinfunction "GND_5") (pintype "power_in"))
      (node (ref "IC3") (pin "7") (pinfunction "GND_7") (pintype "power_in"))
      (node (ref "IC31") (pin "6") (pinfunction "GND_6") (pintype "power_in"))
      (node (ref "IC31") (pin "7") (pinfunction "GND_7") (pintype "power_in"))
      (node (ref "IC4") (pin "3") (pinfunction "DE_3") (pintype "input"))
      (node (ref "IC4") (pin "5") (pinfunction "GND_5") (pintype "power_in"))
      (node (ref "X8") (pin "19") (pinfunction "GND_19") (pintype "bidirectional"))
    )
    (net (code "18") (name "GND3") (class "Default")
      (node (ref "C45") (pin "2") (pinfunction "2_2") (pintype "passive"))
      (node (ref "C48") (pin "2") (pinfunction "2_2") (pintype "passive"))
      (node (ref "IC5") (pin "10") (pinfunction "GND_10") (pintype "power_in"))
      (node (ref "IC5") (pin "24") (pinfunction "EN_24") (pintype "input"))
      (node (ref "IC5") (pin "25") (pinfunction "SHDN_25") (pintype "input"))
      (node (ref "X9") (pin "19") (pinfunction "GND_19") (pintype "bidirectional"))
    )
    (net (code "19") (name "GND4") (class "Default")
      (node (ref "X10") (pin "19") (pinfunction "GND_19") (pintype "bidirectional"))
      (node (ref "X5") (pin "P$1") (pinfunction "S_P$1") (pintype "passive"))
    )
    (net (code "20") (name "GND5") (class "Default")
      (node (ref "OK3") (pin "2") (pinfunction "C_2") (pintype "passive"))
      (node (ref "R15") (pin "1") (pinfunction "1_1") (pintype "passive"))
      (node (ref "R17") (pin "1") (pinfunction "1_1") (pintype "passive"))
      (node (ref "R20") (pin "1") (pinfunction "1_1") (pintype "passive"))
      (node (ref "SV5") (pin "7") (pinfunction "7_7") (pintype "passive"))
      (node (ref "SV5") (pin "8") (pinfunction "8_8") (pintype "passive"))
      (node (ref "X11") (pin "19") (pinfunction "GND_19") (pintype "bidirectional"))
    )
    (net (code "21") (name "GND6") (class "Default")
      (node (ref "C14") (pin "2") (pinfunction "2_2") (pintype "passive"))
      (node (ref "D4") (pin "1") (pinfunction "A_1") (pintype "passive"))
      (node (ref "IC6") (pin "5") (pinfunction "VSS_5") (pintype "power_in"))
      (node (ref "IC6") (pin "TGND") (pinfunction "TGND_TGND") (pintype "power_in"))
      (node (ref "X6") (pin "P$3") (pinfunction "S_P$3") (pintype "passive"))
    )
    (net (code "22") (name "Net-(C1-Pad1)") (class "Default")
      (node (ref "C1") (pin "1") (pinfunction "1_1") (pintype "passive"))
      (node (ref "L10") (pin "1") (pinfunction "1_1") (pintype "passive"))
      (node (ref "X2") (pin "1") (pinfunction "1_1") (pintype "passive"))
    )
    (net (code "23") (name "Net-(D1-A)") (class "Default")
      (node (ref "D1") (pin "1") (pinfunction "A_1") (pintype "passive"))
      (node (ref "LED5") (pin "C") (pinfunction "C_C") (pintype "passive"))
      (node (ref "T4") (pin "3") (pinfunction "C_3") (pintype "passive"))
    )
    (net (code "24") (name "Net-(D1-C)") (class "Default")
      (node (ref "D1") (pin "3") (pinfunction "C_3") (pintype "passive"))
      (node (ref "R10") (pin "1") (pinfunction "1_1") (pintype "passive"))
      (node (ref "R12") (pin "1") (pinfunction "1_1") (pintype "passive"))
      (node (ref "SV5") (pin "11") (pinfunction "11_11") (pintype "passive"))
      (node (ref "SV5") (pin "3") (pinfunction "3_3") (pintype "passive"))
    )
    (net (code "25") (name "Net-(D2-A)") (class "Default")
      (node (ref "D2") (pin "1") (pinfunction "A_1") (pintype "passive"))
      (node (ref "OK1") (pin "2") (pinfunction "C_2") (pintype "passive"))
      (node (ref "SV5") (pin "5") (pinfunction "5_5") (pintype "passive"))
    )
    (net (code "26") (name "Net-(D2-C)") (class "Default")
      (node (ref "D2") (pin "3") (pinfunction "C_3") (pintype "passive"))
      (node (ref "R19") (pin "1") (pinfunction "1_1") (pintype "passive"))
      (node (ref "SV5") (pin "12") (pinfunction "12_12") (pintype "passive"))
      (node (ref "SV5") (pin "4") (pinfunction "4_4") (pintype "passive"))
    )
    (net (code "27") (name "Net-(D3-PadC)") (class "Default")
      (node (ref "D3") (pin "C") (pinfunction "C_C") (pintype "passive"))
      (node (ref "R6") (pin "2") (pinfunction "2_2") (pintype "passive"))
    )
    (net (code "28") (name "Net-(D4-C)") (class "Default")
      (node (ref "D4") (pin "3") (pinfunction "C_3") (pintype "passive"))
      (node (ref "IC6") (pin "6") (pinfunction "LBUS_6") (pintype "bidirectional"))
      (node (ref "JP1") (pin "2") (pinfunction "2_2") (pintype "passive"))
      (node (ref "X6") (pin "P$2") (pinfunction "S_P$2") (pintype "passive"))
    )
    (net (code "29") (name "Net-(IC3A-I0)") (class "Default")
      (node (ref "IC3") (pin "2") (pinfunction "I0_2") (pintype "input"))
      (node (ref "IC3") (pin "3") (pinfunction "I1_3") (pintype "input"))
      (node (ref "IC3") (pin "4") (pinfunction "O_4") (pintype "output"))
    )
    (net (code "30") (name "Net-(IC3B-I0)") (class "Default")
      (node (ref "IC3") (pin "5") (pinfunction "I0_5") (pintype "input"))
      (node (ref "X8") (pin "1") (pinfunction "TXEN_1") (pintype "bidirectional"))
    )
    (net (code "31") (name "Net-(IC4A-A)") (class "Default")
      (node (ref "IC4") (pin "6") (pinfunction "A_6") (pintype "passive"))
      (node (ref "R22") (pin "1") (pinfunction "1_1") (pintype "passive"))
    )
    (net (code "32") (name "Net-(IC4A-B)") (class "Default")
      (node (ref "IC4") (pin "7") (pinfunction "B_7") (pintype "passive"))
      (node (ref "R22") (pin "2") (pinfunction "2_2") (pintype "passive"))
    )
    (net (code "33") (name "Net-(IC5A-C1+)") (class "Default")
      (node (ref "C40") (pin "2") (pinfunction "2_2") (pintype "passive"))
      (node (ref "IC5") (pin "12") (pinfunction "C1+_12") (pintype "passive"))
    )
    (net (code "34") (name "Net-(IC5A-C1-)") (class "Default")
      (node (ref "C40") (pin "1") (pinfunction "1_1") (pintype "passive"))
      (node (ref "IC5") (pin "14") (pinfunction "C1-_14") (pintype "passive"))
    )
    (net (code "35") (name "Net-(IC5A-C2+)") (class "Default")
      (node (ref "C41") (pin "1") (pinfunction "1_1") (pintype "passive"))
      (node (ref "IC5") (pin "15") (pinfunction "C2+_15") (pintype "passive"))
    )
    (net (code "36") (name "Net-(IC5A-R1IN)") (class "Default")
      (node (ref "IC5") (pin "9") (pinfunction "R1IN_9") (pintype "input"))
      (node (ref "X4") (pin "8") (pinfunction "8_8") (pintype "passive"))
    )
    (net (code "37") (name "Net-(IC5A-R1OUT)") (class "Default")
      (node (ref "IC5") (pin "8") (pinfunction "R1OUT_8") (pintype "output"))
      (node (ref "X9") (pin "3") (pinfunction "RTS_3") (pintype "bidirectional"))
    )
    (net (code "38") (name "Net-(IC5A-R2IN)") (class "Default")
      (node (ref "IC5") (pin "4") (pinfunction "R2IN_4") (pintype "input"))
      (node (ref "X4") (pin "6") (pinfunction "6_6") (pintype "passive"))
    )
    (net (code "39") (name "Net-(IC5A-R2OUT)") (class "Default")
      (node (ref "IC5") (pin "5") (pinfunction "R2OUT_5") (pintype "output"))
      (node (ref "X9") (pin "4") (pinfunction "DTR_4") (pintype "bidirectional"))
    )
    (net (code "40") (name "Net-(IC5A-R3IN)") (class "Default")
      (node (ref "IC5") (pin "27") (pinfunction "R3IN_27") (pintype "input"))
      (node (ref "X4") (pin "1") (pinfunction "1_1") (pintype "passive"))
    )
    (net (code "41") (name "Net-(IC5A-R3OUT)") (class "Default")
      (node (ref "IC5") (pin "26") (pinfunction "R3OUT_26") (pintype "output"))
      (node (ref "X9") (pin "11") (pinfunction "DCD_11") (pintype "bidirectional"))
    )
    (net (code "42") (name "Net-(IC5A-R4IN)") (class "Default")
      (node (ref "IC5") (pin "23") (pinfunction "R4IN_23") (pintype "input"))
      (node (ref "X4") (pin "2") (pinfunction "2_2") (pintype "passive"))
    )
    (net (code "43") (name "Net-(IC5A-R4OUT)") (class "Default")
      (node (ref "IC5") (pin "22") (pinfunction "R4OUT_22") (pintype "output"))
      (node (ref "X9") (pin "8") (pinfunction "RXD_8") (pintype "bidirectional"))
    )
    (net (code "44") (name "Net-(IC5A-R5IN)") (class "Default")
      (node (ref "IC5") (pin "18") (pinfunction "R5IN_18") (pintype "input"))
      (node (ref "X4") (pin "9") (pinfunction "9_9") (pintype "passive"))
    )
    (net (code "45") (name "Net-(IC5A-R5OUT)") (class "Default")
      (node (ref "IC5") (pin "19") (pinfunction "R5OUT_19") (pintype "output"))
      (node (ref "X9") (pin "9") (pinfunction "RI_9") (pintype "bidirectional"))
    )
    (net (code "46") (name "Net-(IC5A-T1IN)") (class "Default")
      (node (ref "IC5") (pin "7") (pinfunction "T1IN_7") (pintype "input"))
      (node (ref "X9") (pin "5") (pinfunction "TXD_5") (pintype "bidirectional"))
    )
    (net (code "47") (name "Net-(IC5A-T1OUT)") (class "Default")
      (node (ref "IC5") (pin "2") (pinfunction "T1OUT_2") (pintype "output"))
      (node (ref "X4") (pin "3") (pinfunction "3_3") (pintype "passive"))
    )
    (net (code "48") (name "Net-(IC5A-T2IN)") (class "Default")
      (node (ref "IC5") (pin "6") (pinfunction "T2IN_6") (pintype "input"))
      (node (ref "X9") (pin "10") (pinfunction "DSR_10") (pintype "bidirectional"))
    )
    (net (code "49") (name "Net-(IC5A-T2OUT)") (class "Default")
      (node (ref "IC5") (pin "3") (pinfunction "T2OUT_3") (pintype "output"))
      (node (ref "X4") (pin "4") (pinfunction "4_4") (pintype "passive"))
    )
    (net (code "50") (name "Net-(IC5A-T3IN)") (class "Default")
      (node (ref "IC5") (pin "20") (pinfunction "T3IN_20") (pintype "input"))
      (node (ref "X9") (pin "12") (pinfunction "CTS_12") (pintype "bidirectional"))
    )
    (net (code "51") (name "Net-(IC5A-T3OUT)") (class "Default")
      (node (ref "IC5") (pin "1") (pinfunction "T3OUT_1") (pintype "output"))
      (node (ref "X4") (pin "7") (pinfunction "7_7") (pintype "passive"))
    )
    (net (code "52") (name "Net-(IC5A-V+)") (class "Default")
      (node (ref "C44") (pin "1") (pinfunction "1_1") (pintype "passive"))
      (node (ref "IC5") (pin "13") (pinfunction "V+_13") (pintype "passive"))
    )
    (net (code "53") (name "Net-(IC5A-V-)") (class "Default")
      (node (ref "C45") (pin "1") (pinfunction "1_1") (pintype "passive"))
      (node (ref "IC5") (pin "17") (pinfunction "V-_17") (pintype "passive"))
    )
    (net (code "54") (name "Net-(IC6-CS)") (class "Default")
      (node (ref "IC6") (pin "2") (pinfunction "CS_2") (pintype "input"))
      (node (ref "X12") (pin "1") (pinfunction "TXEN_1") (pintype "bidirectional"))
    )
    (net (code "55") (name "Net-(IC6-RXD)") (class "Default")
      (node (ref "IC6") (pin "1") (pinfunction "RXD_1") (pintype "input"))
      (node (ref "X12") (pin "8") (pinfunction "RXD_8") (pintype "bidirectional"))
    )
    (net (code "56") (name "Net-(IC6-TXD)") (class "Default")
      (node (ref "IC6") (pin "4") (pinfunction "TXD_4") (pintype "output"))
      (node (ref "X12") (pin "5") (pinfunction "TXD_5") (pintype "bidirectional"))
    )
    (net (code "57") (name "Net-(IC6-VBB)") (class "Default")
      (node (ref "IC6") (pin "7") (pinfunction "VBB_7") (pintype "power_in"))
      (node (ref "X6") (pin "P$1") (pinfunction "S_P$1") (pintype "passive"))
    )
    (net (code "58") (name "Net-(IC6-VREN)") (class "Default")
      (node (ref "C14") (pin "1") (pinfunction "1_1") (pintype "passive"))
      (node (ref "IC6") (pin "8") (pinfunction "VREN_8") (pintype "output"))
    )
    (net (code "59") (name "Net-(IC7A-OUTB)") (class "Default")
      (node (ref "IC7") (pin "14") (pinfunction "OUTB_14") (pintype "output"))
      (node (ref "X14") (pin "5") (pinfunction "TXD_5") (pintype "bidirectional"))
    )
    (net (code "60") (name "Net-(IC7B-OUTB)") (class "Default")
      (node (ref "IC7") (pin "13") (pinfunction "OUTB_13") (pintype "output"))
      (node (ref "X14") (pin "3") (pinfunction "RTS_3") (pintype "bidirectional"))
    )
    (net (code "61") (name "Net-(IC7C-INB)") (class "Default")
      (node (ref "IC7") (pin "12") (pinfunction "INB_12") (pintype "input"))
      (node (ref "X14") (pin "8") (pinfunction "RXD_8") (pintype "bidirectional"))
    )
    (net (code "62") (name "Net-(IC7D-INB)") (class "Default")
      (node (ref "IC7") (pin "11") (pinfunction "INB_11") (pintype "input"))
      (node (ref "X14") (pin "12") (pinfunction "CTS_12") (pintype "bidirectional"))
    )
    (net (code "63") (name "Net-(IC8A-OUTB)") (class "Default")
      (node (ref "IC8") (pin "14") (pinfunction "OUTB_14") (pintype "output"))
      (node (ref "X14") (pin "4") (pinfunction "DTR_4") (pintype "bidirectional"))
    )
    (net (code "64") (name "Net-(IC8B-OUTB)") (class "Default")
      (node (ref "IC8") (pin "13") (pinfunction "OUTB_13") (pintype "output"))
      (node (ref "X14") (pin "1") (pinfunction "TXEN_1") (pintype "bidirectional"))
    )
    (net (code "65") (name "Net-(IC8C-INB)") (class "Default")
      (node (ref "IC8") (pin "12") (pinfunction "INB_12") (pintype "input"))
      (node (ref "X14") (pin "10") (pinfunction "DSR_10") (pintype "bidirectional"))
    )
    (net (code "66") (name "Net-(IC8D-INB)") (class "Default")
      (node (ref "IC8") (pin "11") (pinfunction "INB_11") (pintype "input"))
      (node (ref "X14") (pin "11") (pinfunction "DCD_11") (pintype "bidirectional"))
    )
    (net (code "67") (name "Net-(IC9A-OUTB)") (class "Default")
      (node (ref "IC9") (pin "14") (pinfunction "OUTB_14") (pintype "output"))
      (node (ref "X14") (pin "2") (pinfunction "GPIO_2") (pintype "bidirectional"))
    )
    (net (code "68") (name "Net-(IC9C-INB)") (class "Default")
      (node (ref "IC9") (pin "12") (pinfunction "INB_12") (pintype "input"))
      (node (ref "X14") (pin "9") (pinfunction "RI_9") (pintype "bidirectional"))
    )
    (net (code "69") (name "Net-(IC10-3V3OUT)") (class "Default")
      (node (ref "C18") (pin "1") (pinfunction "1_1") (pintype "passive"))
      (node (ref "IC10") (pin "17") (pinfunction "3V3OUT_17") (pintype "output"))
    )
    (net (code "70") (name "Net-(IC10-CBUS0)") (class "Default")
      (node (ref "IC10") (pin "23") (pinfunction "CBUS0_23") (pintype "bidirectional"))
      (node (ref "R4") (pin "2") (pinfunction "2_2") (pintype "passive"))
    )
    (net (code "71") (name "Net-(IC10-CBUS1)") (class "Default")
      (node (ref "IC10") (pin "22") (pinfunction "CBUS1_22") (pintype "bidirectional"))
      (node (ref "R3") (pin "2") (pinfunction "2_2") (pintype "passive"))
    )
    (net (code "72") (name "Net-(IC10-CBUS2)") (class "Default")
      (node (ref "IC10") (pin "13") (pinfunction "CBUS2_13") (pintype "bidirectional"))
      (node (ref "IC8") (pin "4") (pinfunction "INA_4") (pintype "input"))
      (node (ref "R9") (pin "2") (pinfunction "2_2") (pintype "passive"))
    )
    (net (code "73") (name "Net-(IC10-CBUS4)") (class "Default")
      (node (ref "IC10") (pin "12") (pinfunction "CBUS4_12") (pintype "bidirectional"))
      (node (ref "IC9") (pin "3") (pinfunction "INA_3") (pintype "input"))
    )
    (net (code "74") (name "Net-(IC10-RXD)") (class "Default")
      (node (ref "IC10") (pin "5") (pinfunction "RXD_5") (pintype "input"))
      (node (ref "IC7") (pin "5") (pinfunction "OUTA_5") (pintype "output"))
    )
    (net (code "75") (name "Net-(IC10-TXD)") (class "Default")
      (node (ref "IC10") (pin "1") (pinfunction "TXD_1") (pintype "output"))
      (node (ref "IC7") (pin "3") (pinfunction "INA_3") (pintype "input"))
    )
    (net (code "76") (name "Net-(IC10-USBDM)") (class "Default")
      (node (ref "IC10") (pin "16") (pinfunction "USBDM_16") (pintype "bidirectional"))
      (node (ref "X2") (pin "2") (pinfunction "2_2") (pintype "passive"))
    )
    (net (code "77") (name "Net-(IC10-USBDP)") (class "Default")
      (node (ref "IC10") (pin "15") (pinfunction "USBDP_15") (pintype "bidirectional"))
      (node (ref "X2") (pin "3") (pinfunction "3_3") (pintype "passive"))
    )
    (net (code "78") (name "Net-(IC10-VCC)") (class "Default")
      (node (ref "C5") (pin "1") (pinfunction "1_1") (pintype "passive"))
      (node (ref "C6") (pin "1") (pinfunction "1_1") (pintype "passive"))
      (node (ref "IC10") (pin "20") (pinfunction "VCC_20") (pintype "power_in"))
      (node (ref "IC10") (pin "4") (pinfunction "VCCIO_4") (pintype "power_in"))
      (node (ref "L10") (pin "2") (pinfunction "2_2") (pintype "passive"))
      (node (ref "Q1") (pin "1") (pinfunction "S_1") (pintype "passive"))
      (node (ref "Q1") (pin "2") (pinfunction "S_2") (pintype "passive"))
      (node (ref "Q1") (pin "3") (pinfunction "S_3") (pintype "passive"))
      (node (ref "R2") (pin "1") (pinfunction "1_1") (pintype "passive"))
    )
    (net (code "79") (name "Net-(IC10-~{CTS})") (class "Default")
      (node (ref "IC10") (pin "11") (pinfunction "~{CTS}_11") (pintype "input"))
      (node (ref "IC7") (pin "6") (pinfunction "OUTA_6") (pintype "output"))
    )
    (net (code "80") (name "Net-(IC10-~{DCD})") (class "Default")
      (node (ref "IC10") (pin "10") (pinfunction "~{DCD}_10") (pintype "input"))
      (node (ref "IC8") (pin "6") (pinfunction "OUTA_6") (pintype "output"))
    )
    (net (code "81") (name "Net-(IC10-~{DSR})") (class "Default")
      (node (ref "IC10") (pin "9") (pinfunction "~{DSR}_9") (pintype "input"))
      (node (ref "IC8") (pin "5") (pinfunction "OUTA_5") (pintype "output"))
    )
    (net (code "82") (name "Net-(IC10-~{DTR})") (class "Default")
      (node (ref "IC10") (pin "2") (pinfunction "~{DTR}_2") (pintype "output"))
      (node (ref "IC8") (pin "3") (pinfunction "INA_3") (pintype "input"))
    )
    (net (code "83") (name "Net-(IC10-~{RESET})") (class "Default")
      (node (ref "IC10") (pin "19") (pinfunction "~{RESET}_19") (pintype "input"))
      (node (ref "S1") (pin "2") (pinfunction "S_2") (pintype "passive"))
    )
    (net (code "84") (name "Net-(IC10-~{RI})") (class "Default")
      (node (ref "IC10") (pin "6") (pinfunction "~{RI}_6") (pintype "input"))
      (node (ref "IC9") (pin "5") (pinfunction "OUTA_5") (pintype "output"))
    )
    (net (code "85") (name "Net-(IC10-~{RTS})") (class "Default")
      (node (ref "IC10") (pin "3") (pinfunction "~{RTS}_3") (pintype "output"))
      (node (ref "IC7") (pin "4") (pinfunction "INA_4") (pintype "input"))
    )
    (net (code "86") (name "Net-(IC20A-DE)") (class "Default")
      (node (ref "IC20") (pin "2") (pinfunction "RE/_2") (pintype "input"))
      (node (ref "IC20") (pin "3") (pinfunction "DE_3") (pintype "input"))
      (node (ref "IC3") (pin "1") (pinfunction "O_1") (pintype "output"))
    )
    (net (code "87") (name "Net-(IC20A-DI)") (class "Default")
      (node (ref "IC20") (pin "4") (pinfunction "DI_4") (pintype "input"))
      (node (ref "IC4") (pin "4") (pinfunction "DI_4") (pintype "input"))
      (node (ref "X8") (pin "5") (pinfunction "TXD_5") (pintype "bidirectional"))
    )
    (net (code "88") (name "Net-(IC20A-RO)") (class "Default")
      (node (ref "IC20") (pin "1") (pinfunction "RO_1") (pintype "output"))
      (node (ref "IC4") (pin "1") (pinfunction "RO_1") (pintype "output"))
      (node (ref "X8") (pin "8") (pinfunction "RXD_8") (pintype "bidirectional"))
    )
    (net (code "89") (name "Net-(IC31D-A)") (class "Default")
      (node (ref "IC31") (pin "12") (pinfunction "A_12") (pintype "passive"))
      (node (ref "R30") (pin "1") (pinfunction "1_1") (pintype "passive"))
    )
    (net (code "90") (name "Net-(IC31D-B)") (class "Default")
      (node (ref "IC31") (pin "11") (pinfunction "B_11") (pintype "passive"))
      (node (ref "R30") (pin "2") (pinfunction "2_2") (pintype "passive"))
    )
    (net (code "91") (name "Net-(IC31D-DI)") (class "Default")
      (node (ref "IC31") (pin "5") (pinfunction "DI_5") (pintype "input"))
      (node (ref "SV1") (pin "4") (pinfunction "4_4") (pintype "passive"))
    )
    (net (code "92") (name "Net-(IC31D-RE{slash})") (class "Default")
      (node (ref "IC3") (pin "10") (pinfunction "O_10") (pintype "output"))
      (node (ref "IC31") (pin "3") (pinfunction "RE/_3") (pintype "input"))
      (node (ref "IC4") (pin "2") (pinfunction "RE/_2") (pintype "input"))
    )
    (net (code "93") (name "Net-(IC31D-RO)") (class "Default")
      (node (ref "IC31") (pin "2") (pinfunction "RO_2") (pintype "output"))
      (node (ref "SV1") (pin "3") (pinfunction "3_3") (pintype "passive"))
    )
    (net (code "94") (name "Net-(IC31D-Y)") (class "Default")
      (node (ref "IC31") (pin "9") (pinfunction "Y_9") (pintype "passive"))
      (node (ref "R5") (pin "2") (pinfunction "2_2") (pintype "passive"))
    )
    (net (code "95") (name "Net-(IC31D-Z)") (class "Default")
      (node (ref "IC31") (pin "10") (pinfunction "Z_10") (pintype "passive"))
      (node (ref "R5") (pin "1") (pinfunction "1_1") (pintype "passive"))
    )
    (net (code "96") (name "Net-(JP1-Pad1)") (class "Default")
      (node (ref "JP1") (pin "1") (pinfunction "1_1") (pintype "passive"))
      (node (ref "R6") (pin "1") (pinfunction "1_1") (pintype "passive"))
    )
    (net (code "97") (name "Net-(LED1-PadA)") (class "Default")
      (node (ref "LED1") (pin "A") (pinfunction "A_A") (pintype "passive"))
      (node (ref "R8") (pin "1") (pinfunction "1_1") (pintype "passive"))
    )
    (net (code "98") (name "Net-(LED2-PadC)") (class "Default")
      (node (ref "LED2") (pin "C") (pinfunction "C_C") (pintype "passive"))
      (node (ref "R3") (pin "1") (pinfunction "1_1") (pintype "passive"))
    )
    (net (code "99") (name "Net-(LED3-PadC)") (class "Default")
      (node (ref "LED3") (pin "C") (pinfunction "C_C") (pintype "passive"))
      (node (ref "R4") (pin "1") (pinfunction "1_1") (pintype "passive"))
    )
    (net (code "100") (name "Net-(LED4-PadA)") (class "Default")
      (node (ref "LED4") (pin "A") (pinfunction "A_A") (pintype "passive"))
      (node (ref "R9") (pin "1") (pinfunction "1_1") (pintype "passive"))
    )
    (net (code "101") (name "Net-(LED5-PadA)") (class "Default")
      (node (ref "LED5") (pin "A") (pinfunction "A_A") (pintype "passive"))
      (node (ref "R12") (pin "2") (pinfunction "2_2") (pintype "passive"))
    )
    (net (code "102") (name "Net-(LED6-PadA)") (class "Default")
      (node (ref "LED6") (pin "A") (pinfunction "A_A") (pintype "passive"))
      (node (ref "R19") (pin "2") (pinfunction "2_2") (pintype "passive"))
    )
    (net (code "103") (name "Net-(OK1-A)") (class "Default")
      (node (ref "LED6") (pin "C") (pinfunction "C_C") (pintype "passive"))
      (node (ref "OK1") (pin "1") (pinfunction "A_1") (pintype "passive"))
    )
    (net (code "104") (name "Net-(OK1-BAS)") (class "Default")
      (node (ref "OK1") (pin "6") (pinfunction "BAS_6") (pintype "passive"))
      (node (ref "R18") (pin "1") (pinfunction "1_1") (pintype "passive"))
    )
    (net (code "105") (name "Net-(OK1-EMI)") (class "Default")
      (node (ref "OK1") (pin "4") (pinfunction "EMI_4") (pintype "passive"))
      (node (ref "R18") (pin "2") (pinfunction "2_2") (pintype "passive"))
      (node (ref "R20") (pin "2") (pinfunction "2_2") (pintype "passive"))
      (node (ref "X11") (pin "8") (pinfunction "RXD_8") (pintype "bidirectional"))
    )
    (net (code "106") (name "Net-(OK3-A)") (class "Default")
      (node (ref "OK3") (pin "1") (pinfunction "A_1") (pintype "passive"))
      (node (ref "Q5") (pin "C") (pinfunction "C_C") (pintype "passive"))
    )
    (net (code "107") (name "Net-(OK3-BAS)") (class "Default")
      (node (ref "OK3") (pin "6") (pinfunction "BAS_6") (pintype "passive"))
      (node (ref "R11") (pin "1") (pinfunction "1_1") (pintype "passive"))
    )
    (net (code "108") (name "Net-(OK3-COL)") (class "Default")
      (node (ref "OK3") (pin "5") (pinfunction "COL_5") (pintype "passive"))
      (node (ref "R10") (pin "2") (pinfunction "2_2") (pintype "passive"))
      (node (ref "T4") (pin "1") (pinfunction "B_1") (pintype "passive"))
    )
    (net (code "109") (name "Net-(OK3-EMI)") (class "Default")
      (node (ref "OK3") (pin "4") (pinfunction "EMI_4") (pintype "passive"))
      (node (ref "R11") (pin "2") (pinfunction "2_2") (pintype "passive"))
      (node (ref "SV5") (pin "6") (pinfunction "6_6") (pintype "passive"))
      (node (ref "T4") (pin "2") (pinfunction "E_2") (pintype "passive"))
    )
    (net (code "110") (name "Net-(Q1-G)") (class "Default")
      (node (ref "C4") (pin "2") (pinfunction "2_2") (pintype "passive"))
      (node (ref "Q1") (pin "4") (pinfunction "G_4") (pintype "passive"))
      (node (ref "R1") (pin "1") (pinfunction "1_1") (pintype "passive"))
    )
    (net (code "111") (name "Net-(Q2-PadB)") (class "Default")
      (node (ref "Q2") (pin "B") (pinfunction "B_B") (pintype "passive"))
      (node (ref "Q3") (pin "C") (pinfunction "C_C") (pintype "passive"))
      (node (ref "R15") (pin "2") (pinfunction "2_2") (pintype "passive"))
    )
    (net (code "112") (name "Net-(Q2-PadE)") (class "Default")
      (node (ref "Q2") (pin "E") (pinfunction "E_E") (pintype "passive"))
      (node (ref "Q3") (pin "B") (pinfunction "B_B") (pintype "passive"))
      (node (ref "R14") (pin "2") (pinfunction "2_2") (pintype "passive"))
    )
    (net (code "113") (name "Net-(Q4-PadB)") (class "Default")
      (node (ref "Q4") (pin "B") (pinfunction "B_B") (pintype "passive"))
      (node (ref "Q6") (pin "C") (pinfunction "C_C") (pintype "passive"))
      (node (ref "R17") (pin "2") (pinfunction "2_2") (pintype "passive"))
    )
    (net (code "114") (name "Net-(Q4-PadE)") (class "Default")
      (node (ref "Q4") (pin "E") (pinfunction "E_E") (pintype "passive"))
      (node (ref "Q6") (pin "B") (pinfunction "B_B") (pintype "passive"))
      (node (ref "R16") (pin "2") (pinfunction "2_2") (pintype "passive"))
    )
    (net (code "115") (name "Net-(Q5-PadE)") (class "Default")
      (node (ref "Q5") (pin "E") (pinfunction "E_E") (pintype "passive"))
      (node (ref "R13") (pin "2") (pinfunction "2_2") (pintype "passive"))
    )
    (net (code "116") (name "Net-(X8A-CTS)") (class "Default")
      (node (ref "SV1") (pin "5") (pinfunction "5_5") (pintype "passive"))
      (node (ref "X8") (pin "12") (pinfunction "CTS_12") (pintype "bidirectional"))
    )
    (net (code "117") (name "Net-(X8A-DSR)") (class "Default")
      (node (ref "SV1") (pin "1") (pinfunction "1_1") (pintype "passive"))
      (node (ref "X8") (pin "10") (pinfunction "DSR_10") (pintype "bidirectional"))
    )
    (net (code "118") (name "Net-(X8A-DTR)") (class "Default")
      (node (ref "SV1") (pin "2") (pinfunction "2_2") (pintype "passive"))
      (node (ref "X8") (pin "4") (pinfunction "DTR_4") (pintype "bidirectional"))
    )
    (net (code "119") (name "Net-(X8A-RTS)") (class "Default")
      (node (ref "SV1") (pin "6") (pinfunction "6_6") (pintype "passive"))
      (node (ref "X8") (pin "3") (pinfunction "RTS_3") (pintype "bidirectional"))
    )
    (net (code "120") (name "Net-(X10B-+3.3V)") (class "Default")
      (node (ref "J1") (pin "1") (pinfunction "1_1") (pintype "passive"))
      (node (ref "X10") (pin "16") (pinfunction "+3.3V_16") (pintype "bidirectional"))
    )
    (net (code "121") (name "Net-(X10B-+5V)") (class "Default")
      (node (ref "J1") (pin "3") (pinfunction "3_3") (pintype "passive"))
      (node (ref "X10") (pin "18") (pinfunction "+5V_18") (pintype "bidirectional"))
    )
    (net (code "122") (name "Net-(X10B-VIN)") (class "Default")
      (node (ref "J1") (pin "2") (pinfunction "2_2") (pintype "passive"))
      (node (ref "X10") (pin "7") (pinfunction "VIN_7") (pintype "bidirectional"))
      (node (ref "X5") (pin "P$2") (pinfunction "S_P$2") (pintype "passive"))
    )
    (net (code "123") (name "Net-(X11A-TXD)") (class "Default")
      (node (ref "Q5") (pin "B") (pinfunction "B_B") (pintype "passive"))
      (node (ref "X11") (pin "5") (pinfunction "TXD_5") (pintype "bidirectional"))
    )
    (net (code "124") (name "RI4") (class "Default")
      (node (ref "X10") (pin "9") (pinfunction "RI_9") (pintype "bidirectional"))
      (node (ref "X5") (pin "P$10") (pinfunction "S_P$10") (pintype "passive"))
    )
    (net (code "125") (name "RS422EN") (class "Default")
      (node (ref "IC3") (pin "6") (pinfunction "I1_6") (pintype "input"))
      (node (ref "IC3") (pin "8") (pinfunction "I0_8") (pintype "input"))
      (node (ref "IC3") (pin "9") (pinfunction "I1_9") (pintype "input"))
      (node (ref "IC31") (pin "4") (pinfunction "DE_4") (pintype "input"))
    )
    (net (code "126") (name "RTS4") (class "Default")
      (node (ref "X10") (pin "3") (pinfunction "RTS_3") (pintype "bidirectional"))
      (node (ref "X5") (pin "P$5") (pinfunction "S_P$5") (pintype "passive"))
    )
    (net (code "127") (name "RXD4") (class "Default")
      (node (ref "X10") (pin "8") (pinfunction "RXD_8") (pintype "bidirectional"))
      (node (ref "X5") (pin "P$4") (pinfunction "S_P$4") (pintype "passive"))
    )
    (net (code "128") (name "TXD4") (class "Default")
      (node (ref "X10") (pin "5") (pinfunction "TXD_5") (pintype "bidirectional"))
      (node (ref "X5") (pin "P$3") (pinfunction "S_P$3") (pintype "passive"))
    )
    (net (code "129") (name "VIN1") (class "Default")
      (node (ref "C17") (pin "1") (pinfunction "1_1") (pintype "passive"))
      (node (ref "C19") (pin "1") (pinfunction "1_1") (pintype "passive"))
      (node (ref "C8") (pin "1") (pinfunction "1_1") (pintype "passive"))
      (node (ref "IC7") (pin "10") (pinfunction "ENB_10") (pintype "input"))
      (node (ref "IC7") (pin "16") (pinfunction "VDDB_16") (pintype "power_in"))
      (node (ref "IC8") (pin "10") (pinfunction "ENB_10") (pintype "input"))
      (node (ref "IC8") (pin "16") (pinfunction "VDDB_16") (pintype "power_in"))
      (node (ref "IC9") (pin "10") (pinfunction "ENB_10") (pintype "input"))
      (node (ref "IC9") (pin "16") (pinfunction "VDDB_16") (pintype "power_in"))
      (node (ref "X14") (pin "7") (pinfunction "VIN_7") (pintype "bidirectional"))
    )
    (net (code "130") (name "unconnected-(C41-Pad2)") (class "Default")
      (node (ref "C41") (pin "2") (pinfunction "2_2") (pintype "passive"))
    )
    (net (code "131") (name "unconnected-(D3-PadA)") (class "Default")
      (node (ref "D3") (pin "A") (pinfunction "A_A") (pintype "passive"))
    )
    (net (code "132") (name "unconnected-(IC5A-C2--Pad16)") (class "Default")
      (node (ref "IC5") (pin "16") (pinfunction "C2-_16") (pintype "passive"))
    )
    (net (code "133") (name "unconnected-(IC5A-T4IN-Pad21)") (class "Default")
      (node (ref "IC5") (pin "21") (pinfunction "T4IN_21") (pintype "input"))
    )
    (net (code "134") (name "unconnected-(IC5A-T4OUT-Pad28)") (class "Default")
      (node (ref "IC5") (pin "28") (pinfunction "T4OUT_28") (pintype "output"))
    )
    (net (code "135") (name "unconnected-(IC6-~{WAKE}-Pad3)") (class "Default")
      (node (ref "IC6") (pin "3") (pinfunction "~{WAKE}_3") (pintype "input"))
    )
    (net (code "136") (name "unconnected-(IC9B-OUTB-Pad13)") (class "Default")
      (node (ref "IC9") (pin "13") (pinfunction "OUTB_13") (pintype "output"))
    )
    (net (code "137") (name "unconnected-(IC9D-OUTA-Pad6)") (class "Default")
      (node (ref "IC9") (pin "6") (pinfunction "OUTA_6") (pintype "output"))
    )
    (net (code "138") (name "unconnected-(IC10-OSCI-Pad27)") (class "Default")
      (node (ref "IC10") (pin "27") (pinfunction "OSCI_27") (pintype "input"))
    )
    (net (code "139") (name "unconnected-(IC10-OSCO-Pad28)") (class "Default")
      (node (ref "IC10") (pin "28") (pinfunction "OSCO_28") (pintype "output"))
    )
    (net (code "140") (name "unconnected-(IC10-TEST-Pad26)") (class "Default")
      (node (ref "IC10") (pin "26") (pinfunction "TEST_26") (pintype "input"))
    )
    (net (code "141") (name "unconnected-(IC20A-A-Pad6)") (class "Default")
      (node (ref "IC20") (pin "6") (pinfunction "A_6") (pintype "passive"))
    )
    (net (code "142") (name "unconnected-(IC20A-B-Pad7)") (class "Default")
      (node (ref "IC20") (pin "7") (pinfunction "B_7") (pintype "passive"))
    )
    (net (code "143") (name "unconnected-(R31-Pad1)") (class "Default")
      (node (ref "R31") (pin "1") (pinfunction "1_1") (pintype "passive"))
    )
    (net (code "144") (name "unconnected-(R31-Pad2)") (class "Default")
      (node (ref "R31") (pin "2") (pinfunction "2_2") (pintype "passive"))
    )
    (net (code "145") (name "unconnected-(SV1-Pad7)") (class "Default")
      (node (ref "SV1") (pin "7") (pinfunction "7_7") (pintype "passive"))
    )
    (net (code "146") (name "unconnected-(SV1-Pad8)") (class "Default")
      (node (ref "SV1") (pin "8") (pinfunction "8_8") (pintype "passive"))
    )
    (net (code "147") (name "unconnected-(SV1-Pad9)") (class "Default")
      (node (ref "SV1") (pin "9") (pinfunction "9_9") (pintype "passive"))
    )
    (net (code "148") (name "unconnected-(SV1-Pad10)") (class "Default")
      (node (ref "SV1") (pin "10") (pinfunction "10_10") (pintype "passive"))
    )
    (net (code "149") (name "unconnected-(SV4-Pad1)") (class "Default")
      (node (ref "SV4") (pin "1") (pinfunction "1_1") (pintype "passive"))
    )
    (net (code "150") (name "unconnected-(SV4-Pad2)") (class "Default")
      (node (ref "SV4") (pin "2") (pinfunction "2_2") (pintype "passive"))
    )
    (net (code "151") (name "unconnected-(SV4-Pad3)") (class "Default")
      (node (ref "SV4") (pin "3") (pinfunction "3_3") (pintype "passive"))
    )
    (net (code "152") (name "unconnected-(SV4-Pad4)") (class "Default")
      (node (ref "SV4") (pin "4") (pinfunction "4_4") (pintype "passive"))
    )
    (net (code "153") (name "unconnected-(SV4-Pad5)") (class "Default")
      (node (ref "SV4") (pin "5") (pinfunction "5_5") (pintype "passive"))
    )
    (net (code "154") (name "unconnected-(SV4-Pad6)") (class "Default")
      (node (ref "SV4") (pin "6") (pinfunction "6_6") (pintype "passive"))
    )
    (net (code "155") (name "unconnected-(SV4-Pad7)") (class "Default")
      (node (ref "SV4") (pin "7") (pinfunction "7_7") (pintype "passive"))
    )
    (net (code "156") (name "unconnected-(SV4-Pad8)") (class "Default")
      (node (ref "SV4") (pin "8") (pinfunction "8_8") (pintype "passive"))
    )
    (net (code "157") (name "unconnected-(SV5-Pad1)") (class "Default")
      (node (ref "SV5") (pin "1") (pinfunction "1_1") (pintype "passive"))
    )
    (net (code "158") (name "unconnected-(SV5-Pad2)") (class "Default")
      (node (ref "SV5") (pin "2") (pinfunction "2_2") (pintype "passive"))
    )
    (net (code "159") (name "unconnected-(SV5-Pad9)") (class "Default")
      (node (ref "SV5") (pin "9") (pinfunction "9_9") (pintype "passive"))
    )
    (net (code "160") (name "unconnected-(SV5-Pad10)") (class "Default")
      (node (ref "SV5") (pin "10") (pinfunction "10_10") (pintype "passive"))
    )
    (net (code "161") (name "unconnected-(SV6-Pad1)") (class "Default")
      (node (ref "SV6") (pin "1") (pinfunction "1_1") (pintype "passive"))
    )
    (net (code "162") (name "unconnected-(SV6-Pad2)") (class "Default")
      (node (ref "SV6") (pin "2") (pinfunction "2_2") (pintype "passive"))
    )
    (net (code "163") (name "unconnected-(SV6-Pad3)") (class "Default")
      (node (ref "SV6") (pin "3") (pinfunction "3_3") (pintype "passive"))
    )
    (net (code "164") (name "unconnected-(SV6-Pad4)") (class "Default")
      (node (ref "SV6") (pin "4") (pinfunction "4_4") (pintype "passive"))
    )
    (net (code "165") (name "unconnected-(SV6-Pad5)") (class "Default")
      (node (ref "SV6") (pin "5") (pinfunction "5_5") (pintype "passive"))
    )
    (net (code "166") (name "unconnected-(SV6-Pad6)") (class "Default")
      (node (ref "SV6") (pin "6") (pinfunction "6_6") (pintype "passive"))
    )
    (net (code "167") (name "unconnected-(SV6-Pad7)") (class "Default")
      (node (ref "SV6") (pin "7") (pinfunction "7_7") (pintype "passive"))
    )
    (net (code "168") (name "unconnected-(SV6-Pad8)") (class "Default")
      (node (ref "SV6") (pin "8") (pinfunction "8_8") (pintype "passive"))
    )
    (net (code "169") (name "unconnected-(X1A-S-PadP$1)") (class "Default")
      (node (ref "X1") (pin "P$1") (pinfunction "S_P$1") (pintype "passive"))
    )
    (net (code "170") (name "unconnected-(X1B-S-PadP$10)") (class "Default")
      (node (ref "X1") (pin "P$10") (pinfunction "S_P$10") (pintype "passive"))
    )
    (net (code "171") (name "unconnected-(X1C-S-PadP$2)") (class "Default")
      (node (ref "X1") (pin "P$2") (pinfunction "S_P$2") (pintype "passive"))
    )
    (net (code "172") (name "unconnected-(X1D-S-PadP$3)") (class "Default")
      (node (ref "X1") (pin "P$3") (pinfunction "S_P$3") (pintype "passive"))
    )
    (net (code "173") (name "unconnected-(X1E-S-PadP$4)") (class "Default")
      (node (ref "X1") (pin "P$4") (pinfunction "S_P$4") (pintype "passive"))
    )
    (net (code "174") (name "unconnected-(X1F-S-PadP$5)") (class "Default")
      (node (ref "X1") (pin "P$5") (pinfunction "S_P$5") (pintype "passive"))
    )
    (net (code "175") (name "unconnected-(X1G-S-PadP$6)") (class "Default")
      (node (ref "X1") (pin "P$6") (pinfunction "S_P$6") (pintype "passive"))
    )
    (net (code "176") (name "unconnected-(X1H-S-PadP$7)") (class "Default")
      (node (ref "X1") (pin "P$7") (pinfunction "S_P$7") (pintype "passive"))
    )
    (net (code "177") (name "unconnected-(X1I-S-PadP$8)") (class "Default")
      (node (ref "X1") (pin "P$8") (pinfunction "S_P$8") (pintype "passive"))
    )
    (net (code "178") (name "unconnected-(X1J-S-PadP$9)") (class "Default")
      (node (ref "X1") (pin "P$9") (pinfunction "S_P$9") (pintype "passive"))
    )
    (net (code "179") (name "unconnected-(X2-Pad4)") (class "Default")
      (node (ref "X2") (pin "4") (pinfunction "4_4") (pintype "passive"))
    )
    (net (code "180") (name "unconnected-(X4-Pad5)") (class "Default")
      (node (ref "X4") (pin "5") (pinfunction "5_5") (pintype "passive"))
    )
    (net (code "181") (name "unconnected-(X4-PadG1)") (class "Default")
      (node (ref "X4") (pin "G1") (pinfunction "G1_G1") (pintype "passive"))
    )
    (net (code "182") (name "unconnected-(X4-PadG2)") (class "Default")
      (node (ref "X4") (pin "G2") (pinfunction "G2_G2") (pintype "passive"))
    )
    (net (code "183") (name "unconnected-(X7A-S-PadP$1)") (class "Default")
      (node (ref "X7") (pin "P$1") (pinfunction "S_P$1") (pintype "passive"))
    )
    (net (code "184") (name "unconnected-(X7B-S-PadP$2)") (class "Default")
      (node (ref "X7") (pin "P$2") (pinfunction "S_P$2") (pintype "passive"))
    )
    (net (code "185") (name "unconnected-(X7C-S-PadP$3)") (class "Default")
      (node (ref "X7") (pin "P$3") (pinfunction "S_P$3") (pintype "passive"))
    )
    (net (code "186") (name "unconnected-(X7D-S-PadP$4)") (class "Default")
      (node (ref "X7") (pin "P$4") (pinfunction "S_P$4") (pintype "passive"))
    )
    (net (code "187") (name "unconnected-(X8A-DCD-Pad11)") (class "Default")
      (node (ref "X8") (pin "11") (pinfunction "DCD_11") (pintype "bidirectional"))
    )
    (net (code "188") (name "unconnected-(X8A-GPIO-Pad2)") (class "Default")
      (node (ref "X8") (pin "2") (pinfunction "GPIO_2") (pintype "bidirectional"))
    )
    (net (code "189") (name "unconnected-(X8A-RI-Pad9)") (class "Default")
      (node (ref "X8") (pin "9") (pinfunction "RI_9") (pintype "bidirectional"))
    )
    (net (code "190") (name "unconnected-(X8A-RST-Pad6)") (class "Default")
      (node (ref "X8") (pin "6") (pinfunction "RST_6") (pintype "bidirectional"))
    )
    (net (code "191") (name "unconnected-(X8B-+1.8V-Pad14)") (class "Default")
      (node (ref "X8") (pin "14") (pinfunction "+1.8V_14") (pintype "bidirectional"))
    )
    (net (code "192") (name "unconnected-(X8B-+3.3V-Pad16)") (class "Default")
      (node (ref "X8") (pin "16") (pinfunction "+3.3V_16") (pintype "bidirectional"))
    )
    (net (code "193") (name "unconnected-(X8B-+12V-Pad20)") (class "Default")
      (node (ref "X8") (pin "20") (pinfunction "+12V_20") (pintype "bidirectional"))
    )
    (net (code "194") (name "unconnected-(X9A-GPIO-Pad2)") (class "Default")
      (node (ref "X9") (pin "2") (pinfunction "GPIO_2") (pintype "bidirectional"))
    )
    (net (code "195") (name "unconnected-(X9A-RST-Pad6)") (class "Default")
      (node (ref "X9") (pin "6") (pinfunction "RST_6") (pintype "bidirectional"))
    )
    (net (code "196") (name "unconnected-(X9A-TXEN-Pad1)") (class "Default")
      (node (ref "X9") (pin "1") (pinfunction "TXEN_1") (pintype "bidirectional"))
    )
    (net (code "197") (name "unconnected-(X9B-+1.8V-Pad14)") (class "Default")
      (node (ref "X9") (pin "14") (pinfunction "+1.8V_14") (pintype "bidirectional"))
    )
    (net (code "198") (name "unconnected-(X9B-+3.3V-Pad16)") (class "Default")
      (node (ref "X9") (pin "16") (pinfunction "+3.3V_16") (pintype "bidirectional"))
    )
    (net (code "199") (name "unconnected-(X9B-+12V-Pad20)") (class "Default")
      (node (ref "X9") (pin "20") (pinfunction "+12V_20") (pintype "bidirectional"))
    )
    (net (code "200") (name "unconnected-(X10A-GPIO-Pad2)") (class "Default")
      (node (ref "X10") (pin "2") (pinfunction "GPIO_2") (pintype "bidirectional"))
    )
    (net (code "201") (name "unconnected-(X10A-RST-Pad6)") (class "Default")
      (node (ref "X10") (pin "6") (pinfunction "RST_6") (pintype "bidirectional"))
    )
    (net (code "202") (name "unconnected-(X10A-TXEN-Pad1)") (class "Default")
      (node (ref "X10") (pin "1") (pinfunction "TXEN_1") (pintype "bidirectional"))
    )
    (net (code "203") (name "unconnected-(X10B-+1.8V-Pad14)") (class "Default")
      (node (ref "X10") (pin "14") (pinfunction "+1.8V_14") (pintype "bidirectional"))
    )
    (net (code "204") (name "unconnected-(X10B-+12V-Pad20)") (class "Default")
      (node (ref "X10") (pin "20") (pinfunction "+12V_20") (pintype "bidirectional"))
    )
    (net (code "205") (name "unconnected-(X11A-CTS-Pad12)") (class "Default")
      (node (ref "X11") (pin "12") (pinfunction "CTS_12") (pintype "bidirectional"))
    )
    (net (code "206") (name "unconnected-(X11A-DCD-Pad11)") (class "Default")
      (node (ref "X11") (pin "11") (pinfunction "DCD_11") (pintype "bidirectional"))
    )
    (net (code "207") (name "unconnected-(X11A-DSR-Pad10)") (class "Default")
      (node (ref "X11") (pin "10") (pinfunction "DSR_10") (pintype "bidirectional"))
    )
    (net (code "208") (name "unconnected-(X11A-DTR-Pad4)") (class "Default")
      (node (ref "X11") (pin "4") (pinfunction "DTR_4") (pintype "bidirectional"))
    )
    (net (code "209") (name "unconnected-(X11A-GPIO-Pad2)") (class "Default")
      (node (ref "X11") (pin "2") (pinfunction "GPIO_2") (pintype "bidirectional"))
    )
    (net (code "210") (name "unconnected-(X11A-RI-Pad9)") (class "Default")
      (node (ref "X11") (pin "9") (pinfunction "RI_9") (pintype "bidirectional"))
    )
    (net (code "211") (name "unconnected-(X11A-RST-Pad6)") (class "Default")
      (node (ref "X11") (pin "6") (pinfunction "RST_6") (pintype "bidirectional"))
    )
    (net (code "212") (name "unconnected-(X11A-RTS-Pad3)") (class "Default")
      (node (ref "X11") (pin "3") (pinfunction "RTS_3") (pintype "bidirectional"))
    )
    (net (code "213") (name "unconnected-(X11A-TXEN-Pad1)") (class "Default")
      (node (ref "X11") (pin "1") (pinfunction "TXEN_1") (pintype "bidirectional"))
    )
    (net (code "214") (name "unconnected-(X11B-+1.8V-Pad14)") (class "Default")
      (node (ref "X11") (pin "14") (pinfunction "+1.8V_14") (pintype "bidirectional"))
    )
    (net (code "215") (name "unconnected-(X11B-+3.3V-Pad16)") (class "Default")
      (node (ref "X11") (pin "16") (pinfunction "+3.3V_16") (pintype "bidirectional"))
    )
    (net (code "216") (name "unconnected-(X12A-CTS-Pad12)") (class "Default")
      (node (ref "X12") (pin "12") (pinfunction "CTS_12") (pintype "bidirectional"))
    )
    (net (code "217") (name "unconnected-(X12A-DCD-Pad11)") (class "Default")
      (node (ref "X12") (pin "11") (pinfunction "DCD_11") (pintype "bidirectional"))
    )
    (net (code "218") (name "unconnected-(X12A-DSR-Pad10)") (class "Default")
      (node (ref "X12") (pin "10") (pinfunction "DSR_10") (pintype "bidirectional"))
    )
    (net (code "219") (name "unconnected-(X12A-DTR-Pad4)") (class "Default")
      (node (ref "X12") (pin "4") (pinfunction "DTR_4") (pintype "bidirectional"))
    )
    (net (code "220") (name "unconnected-(X12A-GPIO-Pad2)") (class "Default")
      (node (ref "X12") (pin "2") (pinfunction "GPIO_2") (pintype "bidirectional"))
    )
    (net (code "221") (name "unconnected-(X12A-RI-Pad9)") (class "Default")
      (node (ref "X12") (pin "9") (pinfunction "RI_9") (pintype "bidirectional"))
    )
    (net (code "222") (name "unconnected-(X12A-RST-Pad6)") (class "Default")
      (node (ref "X12") (pin "6") (pinfunction "RST_6") (pintype "bidirectional"))
    )
    (net (code "223") (name "unconnected-(X12A-RTS-Pad3)") (class "Default")
      (node (ref "X12") (pin "3") (pinfunction "RTS_3") (pintype "bidirectional"))
    )
    (net (code "224") (name "unconnected-(X12B-+1.8V-Pad14)") (class "Default")
      (node (ref "X12") (pin "14") (pinfunction "+1.8V_14") (pintype "bidirectional"))
    )
    (net (code "225") (name "unconnected-(X12B-+3.3V-Pad16)") (class "Default")
      (node (ref "X12") (pin "16") (pinfunction "+3.3V_16") (pintype "bidirectional"))
    )
    (net (code "226") (name "unconnected-(X12B-+5V-Pad18)") (class "Default")
      (node (ref "X12") (pin "18") (pinfunction "+5V_18") (pintype "bidirectional"))
    )
    (net (code "227") (name "unconnected-(X12B-+12V-Pad20)") (class "Default")
      (node (ref "X12") (pin "20") (pinfunction "+12V_20") (pintype "bidirectional"))
    )
    (net (code "228") (name "unconnected-(X12B-GND-Pad19)") (class "Default")
      (node (ref "X12") (pin "19") (pinfunction "GND_19") (pintype "bidirectional"))
    )
    (net (code "229") (name "unconnected-(X12B-VIN-Pad7)") (class "Default")
      (node (ref "X12") (pin "7") (pinfunction "VIN_7") (pintype "bidirectional"))
    )
    (net (code "230") (name "unconnected-(X14A-RST-Pad6)") (class "Default")
      (node (ref "X14") (pin "6") (pinfunction "RST_6") (pintype "bidirectional"))
    )
    (net (code "231") (name "unconnected-(X14B-+1.8V-Pad14)") (class "Default")
      (node (ref "X14") (pin "14") (pinfunction "+1.8V_14") (pintype "bidirectional"))
    )
    (net (code "232") (name "~{PWEN}") (class "Default")
      (node (ref "IC10") (pin "14") (pinfunction "CBUS3_14") (pintype "bidirectional"))
      (node (ref "R1") (pin "2") (pinfunction "2_2") (pintype "passive"))
      (node (ref "R2") (pin "2") (pinfunction "2_2") (pintype "passive"))
    )
  )
)
